# MainCtrl_A6_Pro.net
KiCad netlist of a schematic drawn in Altium Designer
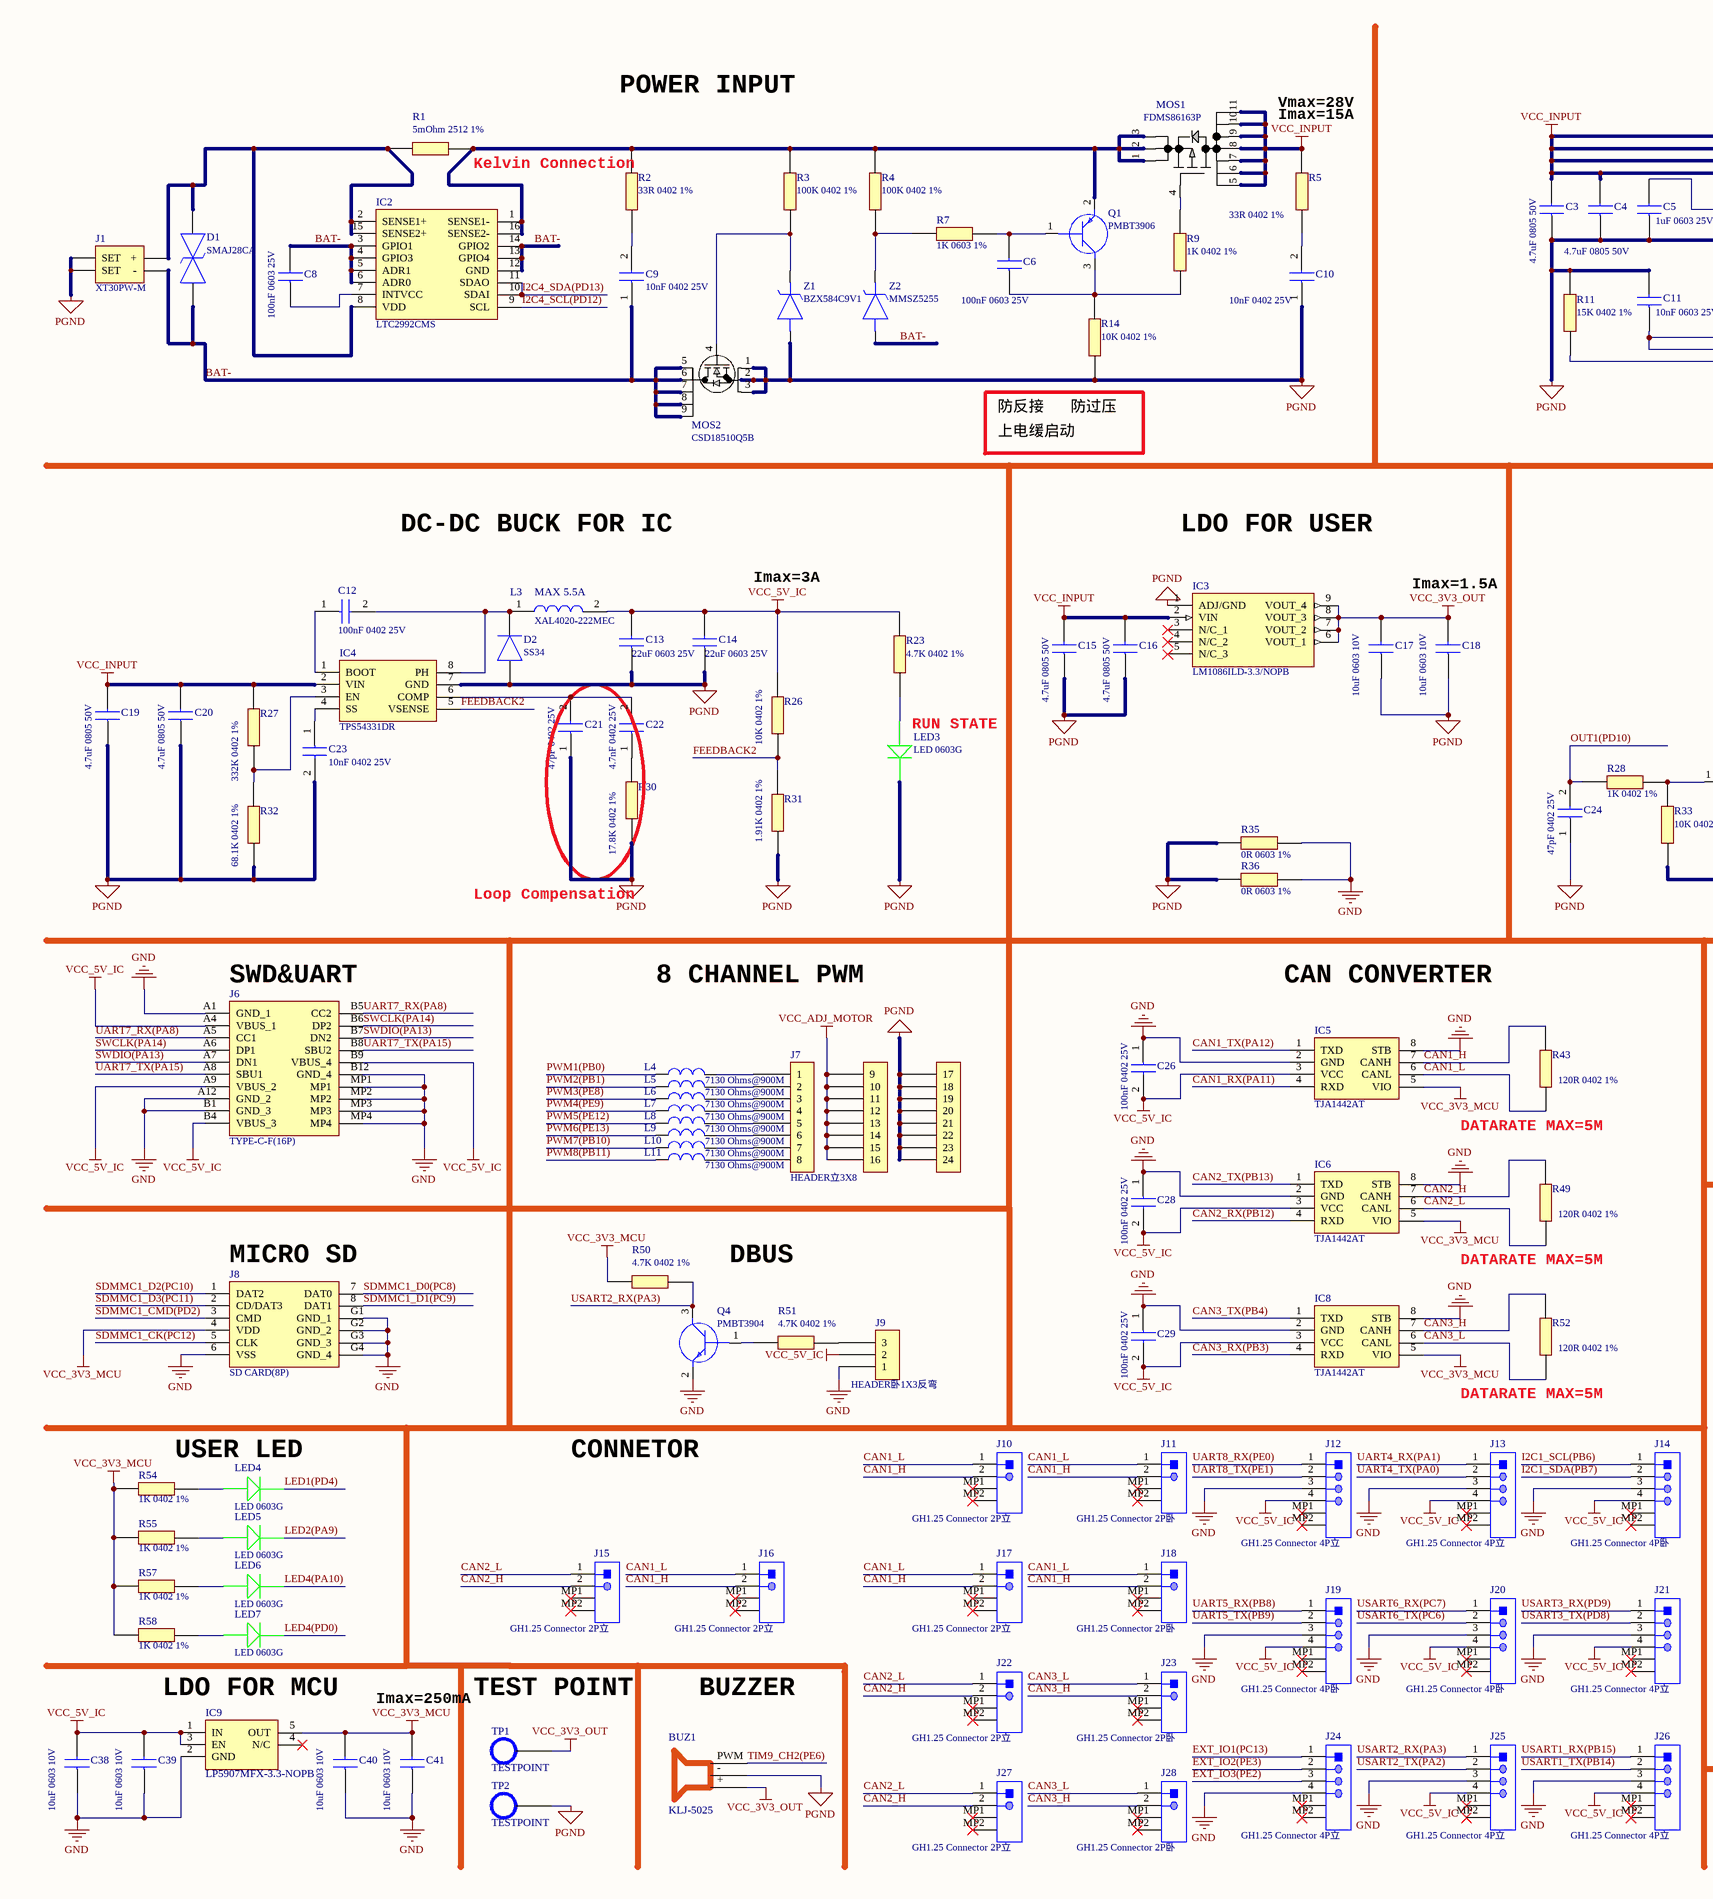
[diagram p0: MainCtrl A6 Pro.SchDoc, left]
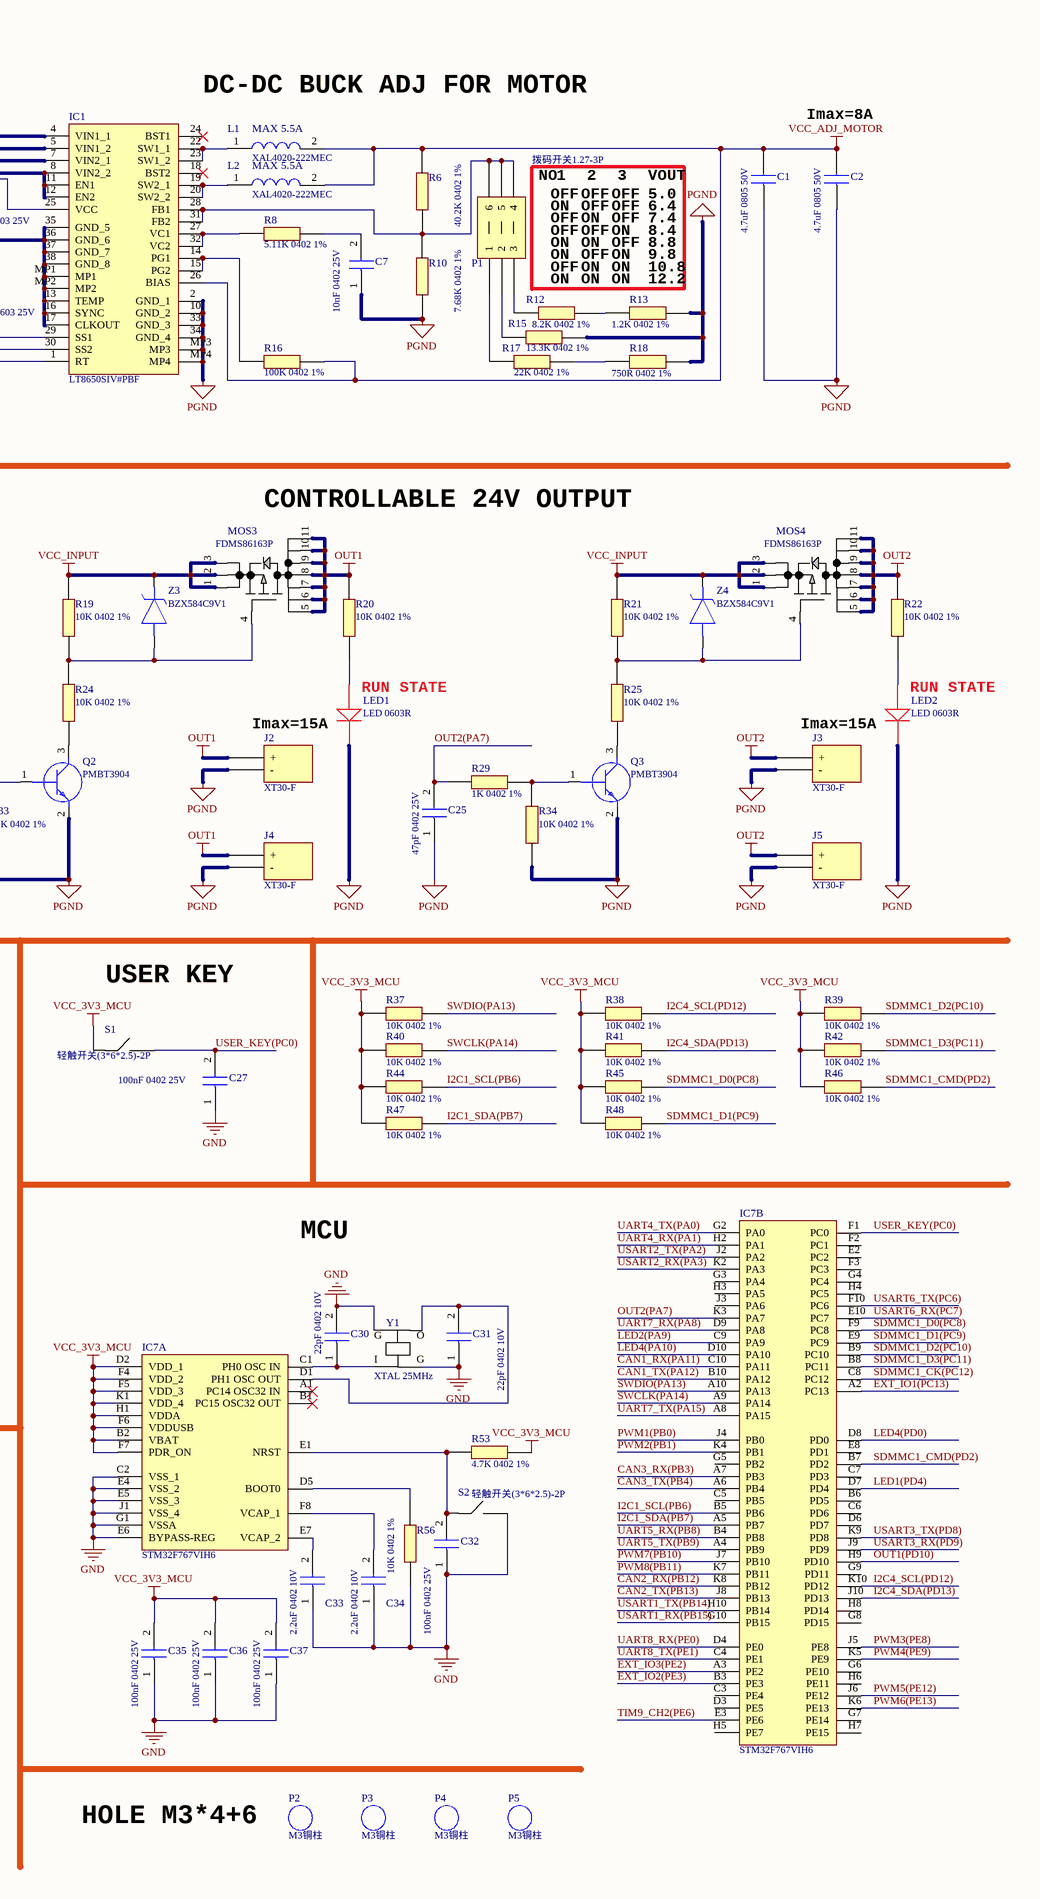
[diagram p1: MainCtrl A6 Pro.SchDoc, right]

(export (version "E")
  (design (tool "Eeschema 10.0.6"))
  (components
    (comp (ref "BUZ1")
      (value "KLJ-5025")
      (footprint "KLJ-5025")
      (description "Buzzer")
      (libsource (lib "Compilation") (part "KLJ-5025"))
    )
    (comp (ref "C1")
      (value "4.7uF 0805 50V")
      (footprint "C0805")
      (description "Capacitor")
      (fields
        (field (name "MANUFACTURER_PART_NUMBER") "0805B104K500CT")
        (field (name "MOUSER PART NUMBER") "791-0805B104K500CT")
      )
      (libsource (lib "Compilation") (part "C0805"))
    )
    (comp (ref "C2")
      (value "4.7uF 0805 50V")
      (footprint "C0805")
      (description "Capacitor")
      (fields
        (field (name "MANUFACTURER_PART_NUMBER") "0805B104K500CT")
        (field (name "MOUSER PART NUMBER") "791-0805B104K500CT")
      )
      (libsource (lib "Compilation") (part "C0805"))
    )
    (comp (ref "C3")
      (value "4.7uF 0805 50V")
      (footprint "C0805")
      (description "Capacitor")
      (fields
        (field (name "MANUFACTURER_PART_NUMBER") "0805B104K500CT")
        (field (name "MOUSER PART NUMBER") "791-0805B104K500CT")
      )
      (libsource (lib "Compilation") (part "C0805"))
    )
    (comp (ref "C4")
      (value "4.7uF 0805 50V")
      (footprint "C0805")
      (description "Capacitor")
      (fields
        (field (name "MANUFACTURER_PART_NUMBER") "0805B104K500CT")
        (field (name "MOUSER PART NUMBER") "791-0805B104K500CT")
      )
      (libsource (lib "Compilation") (part "C0805"))
    )
    (comp (ref "C5")
      (value "1uF 0603 25V")
      (footprint "C0603")
      (description "Capacitor")
      (fields
        (field (name "MANUFACTURER_PART_NUMBER") "0603N470J500CT")
        (field (name "MOUSER PART NUMBER") "791-0603N470J500CT")
      )
      (libsource (lib "Compilation") (part "C0603"))
    )
    (comp (ref "C6")
      (value "100nF 0603 25V")
      (footprint "C0603")
      (description "Capacitor")
      (fields
        (field (name "MANUFACTURER_PART_NUMBER") "0603N470J500CT")
        (field (name "MOUSER PART NUMBER") "791-0603N470J500CT")
      )
      (libsource (lib "Compilation") (part "C0603"))
    )
    (comp (ref "C7")
      (value "10nF 0402 25V")
      (footprint "C0402")
      (description "Capacitor")
      (libsource (lib "Compilation") (part "C0402"))
    )
    (comp (ref "C8")
      (value "100nF 0603 25V")
      (footprint "C0603")
      (description "Capacitor")
      (fields
        (field (name "MANUFACTURER_PART_NUMBER") "0603N470J500CT")
        (field (name "MOUSER PART NUMBER") "791-0603N470J500CT")
      )
      (libsource (lib "Compilation") (part "C0603"))
    )
    (comp (ref "C9")
      (value "10nF 0402 25V")
      (footprint "C0402")
      (description "Capacitor")
      (libsource (lib "Compilation") (part "C0402"))
    )
    (comp (ref "C10")
      (value "10nF 0402 25V")
      (footprint "C0402")
      (description "Capacitor")
      (libsource (lib "Compilation") (part "C0402"))
    )
    (comp (ref "C11")
      (value "10nF 0603 25V")
      (footprint "C0603")
      (description "Capacitor")
      (fields
        (field (name "MANUFACTURER_PART_NUMBER") "0603N470J500CT")
        (field (name "MOUSER PART NUMBER") "791-0603N470J500CT")
      )
      (libsource (lib "Compilation") (part "C0603"))
    )
    (comp (ref "C12")
      (value "100nF 0402 25V")
      (footprint "C0402")
      (description "Capacitor")
      (libsource (lib "Compilation") (part "C0402"))
    )
    (comp (ref "C13")
      (value "22uF 0603 25V")
      (footprint "C0603")
      (description "Capacitor")
      (fields
        (field (name "MANUFACTURER_PART_NUMBER") "0603N470J500CT")
        (field (name "MOUSER PART NUMBER") "791-0603N470J500CT")
      )
      (libsource (lib "Compilation") (part "C0603"))
    )
    (comp (ref "C14")
      (value "22uF 0603 25V")
      (footprint "C0603")
      (description "Capacitor")
      (fields
        (field (name "MANUFACTURER_PART_NUMBER") "0603N470J500CT")
        (field (name "MOUSER PART NUMBER") "791-0603N470J500CT")
      )
      (libsource (lib "Compilation") (part "C0603"))
    )
    (comp (ref "C15")
      (value "4.7uF 0805 50V")
      (footprint "C0805")
      (description "Capacitor")
      (fields
        (field (name "MANUFACTURER_PART_NUMBER") "0805B104K500CT")
        (field (name "MOUSER PART NUMBER") "791-0805B104K500CT")
      )
      (libsource (lib "Compilation") (part "C0805"))
    )
    (comp (ref "C16")
      (value "4.7uF 0805 50V")
      (footprint "C0805")
      (description "Capacitor")
      (fields
        (field (name "MANUFACTURER_PART_NUMBER") "0805B104K500CT")
        (field (name "MOUSER PART NUMBER") "791-0805B104K500CT")
      )
      (libsource (lib "Compilation") (part "C0805"))
    )
    (comp (ref "C17")
      (value "10uF 0603 10V")
      (footprint "C0603")
      (description "Capacitor")
      (fields
        (field (name "MANUFACTURER_PART_NUMBER") "0603N470J500CT")
        (field (name "MOUSER PART NUMBER") "791-0603N470J500CT")
      )
      (libsource (lib "Compilation") (part "C0603"))
    )
    (comp (ref "C18")
      (value "10uF 0603 10V")
      (footprint "C0603")
      (description "Capacitor")
      (fields
        (field (name "MANUFACTURER_PART_NUMBER") "0603N470J500CT")
        (field (name "MOUSER PART NUMBER") "791-0603N470J500CT")
      )
      (libsource (lib "Compilation") (part "C0603"))
    )
    (comp (ref "C19")
      (value "4.7uF 0805 50V")
      (footprint "C0805")
      (description "Capacitor")
      (fields
        (field (name "MANUFACTURER_PART_NUMBER") "0805B104K500CT")
        (field (name "MOUSER PART NUMBER") "791-0805B104K500CT")
      )
      (libsource (lib "Compilation") (part "C0805"))
    )
    (comp (ref "C20")
      (value "4.7uF 0805 50V")
      (footprint "C0805")
      (description "Capacitor")
      (fields
        (field (name "MANUFACTURER_PART_NUMBER") "0805B104K500CT")
        (field (name "MOUSER PART NUMBER") "791-0805B104K500CT")
      )
      (libsource (lib "Compilation") (part "C0805"))
    )
    (comp (ref "C21")
      (value "47pF 0402 25V")
      (footprint "C0402")
      (description "Capacitor")
      (libsource (lib "Compilation") (part "C0402"))
    )
    (comp (ref "C22")
      (value "4.7nF 0402 25V")
      (footprint "C0402")
      (description "Capacitor")
      (libsource (lib "Compilation") (part "C0402"))
    )
    (comp (ref "C23")
      (value "10nF 0402 25V")
      (footprint "C0402")
      (description "Capacitor")
      (libsource (lib "Compilation") (part "C0402"))
    )
    (comp (ref "C24")
      (value "47pF 0402 25V")
      (footprint "C0402")
      (description "Capacitor")
      (libsource (lib "Compilation") (part "C0402"))
    )
    (comp (ref "C25")
      (value "47pF 0402 25V")
      (footprint "C0402")
      (description "Capacitor")
      (libsource (lib "Compilation") (part "C0402"))
    )
    (comp (ref "C26")
      (value "100nF 0402 25V")
      (footprint "C0402")
      (description "Capacitor")
      (libsource (lib "Compilation") (part "C0402"))
    )
    (comp (ref "C27")
      (value "100nF 0402 25V")
      (footprint "C0402")
      (description "Capacitor")
      (libsource (lib "Compilation") (part "C0402"))
    )
    (comp (ref "C28")
      (value "100nF 0402 25V")
      (footprint "C0402")
      (description "Capacitor")
      (libsource (lib "Compilation") (part "C0402"))
    )
    (comp (ref "C29")
      (value "100nF 0402 25V")
      (footprint "C0402")
      (description "Capacitor")
      (libsource (lib "Compilation") (part "C0402"))
    )
    (comp (ref "C30")
      (value "22pF 0402 10V")
      (footprint "C0402")
      (description "Capacitor")
      (libsource (lib "Compilation") (part "C0402"))
    )
    (comp (ref "C31")
      (value "22pF 0402 10V")
      (footprint "C0402")
      (description "Capacitor")
      (libsource (lib "Compilation") (part "C0402"))
    )
    (comp (ref "C32")
      (value "100nF 0402 25V")
      (footprint "C0402")
      (description "Capacitor")
      (libsource (lib "Compilation") (part "C0402"))
    )
    (comp (ref "C33")
      (value "2.2uF 0402 10V")
      (footprint "C0402")
      (description "Capacitor")
      (libsource (lib "Compilation") (part "C0402"))
    )
    (comp (ref "C34")
      (value "2.2uF 0402 10V")
      (footprint "C0402")
      (description "Capacitor")
      (libsource (lib "Compilation") (part "C0402"))
    )
    (comp (ref "C35")
      (value "100nF 0402 25V")
      (footprint "C0402")
      (description "Capacitor")
      (libsource (lib "Compilation") (part "C0402"))
    )
    (comp (ref "C36")
      (value "100nF 0402 25V")
      (footprint "C0402")
      (description "Capacitor")
      (libsource (lib "Compilation") (part "C0402"))
    )
    (comp (ref "C37")
      (value "100nF 0402 25V")
      (footprint "C0402")
      (description "Capacitor")
      (libsource (lib "Compilation") (part "C0402"))
    )
    (comp (ref "C38")
      (value "10uF 0603 10V")
      (footprint "C0603")
      (description "Capacitor")
      (fields
        (field (name "MANUFACTURER_PART_NUMBER") "0603N470J500CT")
        (field (name "MOUSER PART NUMBER") "791-0603N470J500CT")
      )
      (libsource (lib "Compilation") (part "C0603"))
    )
    (comp (ref "C39")
      (value "10uF 0603 10V")
      (footprint "C0603")
      (description "Capacitor")
      (fields
        (field (name "MANUFACTURER_PART_NUMBER") "0603N470J500CT")
        (field (name "MOUSER PART NUMBER") "791-0603N470J500CT")
      )
      (libsource (lib "Compilation") (part "C0603"))
    )
    (comp (ref "C40")
      (value "10uF 0603 10V")
      (footprint "C0603")
      (description "Capacitor")
      (fields
        (field (name "MANUFACTURER_PART_NUMBER") "0603N470J500CT")
        (field (name "MOUSER PART NUMBER") "791-0603N470J500CT")
      )
      (libsource (lib "Compilation") (part "C0603"))
    )
    (comp (ref "C41")
      (value "10uF 0603 10V")
      (footprint "C0603")
      (description "Capacitor")
      (fields
        (field (name "MANUFACTURER_PART_NUMBER") "0603N470J500CT")
        (field (name "MOUSER PART NUMBER") "791-0603N470J500CT")
      )
      (libsource (lib "Compilation") (part "C0603"))
    )
    (comp (ref "D1")
      (value "SMAJ28CA")
      (footprint "SMAJ28CA")
      (description "TVS Diode (Bi-directional)")
      (fields (field (name "MOUSER PART NUMBER") "652-SMAJ28CA"))
      (libsource (lib "Compilation") (part "SMAJ28CA"))
    )
    (comp (ref "D2")
      (value "SS34")
      (footprint "SS34")
      (description "Diode")
      (fields
        (field (name "MANUFACTURER_PART_NUMBER") "SS34LWHRVG")
        (field (name "MOUSER PART NUMBER") "821-SS34LWHRVG")
      )
      (libsource (lib "Compilation") (part "SS34"))
    )
    (comp (ref "IC1")
      (value "LT8650SIV#PBF")
      (footprint "Compilation:LT8650SEV#PBF")
      (description "Integrated Circuit")
      (fields (field (name "MOUSER PART NUMBER") "584-LT8650SIVPBF"))
      (libsource (lib "Compilation") (part "LT8650SIV#PBF"))
    )
    (comp (ref "IC2")
      (value "LTC2992CMS")
      (footprint "Compilation:LTC2992CMS")
      (description "Integrated Circuit")
      (fields
        (field (name "MANUFACTURER_PART_NUMBER") "LTC2992CMS#TRPBF")
        (field (name "MOUSER PART NUMBER") "584-LTC2992CMSTRPBF")
      )
      (libsource (lib "Compilation") (part "LTC2992CMS"))
    )
    (comp (ref "IC3")
      (value "LM1086ILD-3.3/NOPB")
      (footprint "Compilation:LM1086ILD-3.3")
      (description "Integrated Circuit")
      (fields (field (name "MOUSER PART NUMBER") "926-LM1086ILD33NOPB"))
      (libsource (lib "Compilation") (part "LM1086ILD-3.3/NOPB"))
    )
    (comp (ref "IC4")
      (value "TPS54331DR")
      (footprint "TPS54331DR")
      (description "Integrated Circuit")
      (fields (field (name "MOUSER PART NUMBER") "595-TPS54331DR"))
      (libsource (lib "Compilation") (part "TPS54331DR"))
    )
    (comp (ref "IC5")
      (value "TJA1442AT")
      (footprint "Compilation:TJA1442AT")
      (description "Integrated Circuit")
      (fields (field (name "MANUFACTURER_PART_NUMBER") "TJA1442AT/0Z"))
      (libsource (lib "Compilation") (part "TJA1442AT"))
    )
    (comp (ref "IC6")
      (value "TJA1442AT")
      (footprint "Compilation:TJA1442AT")
      (description "Integrated Circuit")
      (fields (field (name "MANUFACTURER_PART_NUMBER") "TJA1442AT/0Z"))
      (libsource (lib "Compilation") (part "TJA1442AT"))
    )
    (comp (ref "IC7")
      (value "STM32F767VIH6")
      (footprint "Compilation:STM32F767VIH6")
      (description "Integrated Circuit")
      (fields (field (name "MOUSER PART NUMBER") "511-STM32F767VIH6"))
      (libsource (lib "Compilation") (part "STM32F767VIH6"))
    )
    (comp (ref "IC8")
      (value "TJA1442AT")
      (footprint "Compilation:TJA1442AT")
      (description "Integrated Circuit")
      (fields (field (name "MANUFACTURER_PART_NUMBER") "TJA1442AT/0Z"))
      (libsource (lib "Compilation") (part "TJA1442AT"))
    )
    (comp (ref "IC9")
      (value "LP5907MFX-3.3-NOPB")
      (footprint "LP5907MFX-3.3")
      (description "Integrated Circuit")
      (fields
        (field (name "MANUFACTURER_PART_NUMBER") "LP5907MFX-3.3/NOPB")
        (field (name "MOUSER PART NUMBER") "595-LP5907MFX-3.3NPB")
      )
      (libsource (lib "Compilation") (part "LP5907MFX-3.3-NOPB"))
    )
    (comp (ref "J1")
      (value "XT30PW-M")
      (footprint "XT30PW-M")
      (description "Connector")
      (libsource (lib "Compilation") (part "XT30PW-M"))
    )
    (comp (ref "J2")
      (value "XT30-F")
      (footprint "XT30-F")
      (description "Connector")
      (libsource (lib "Compilation") (part "XT30-F"))
    )
    (comp (ref "J3")
      (value "XT30-F")
      (footprint "XT30-F")
      (description "Connector")
      (libsource (lib "Compilation") (part "XT30-F"))
    )
    (comp (ref "J4")
      (value "XT30-F")
      (footprint "XT30-F")
      (description "Connector")
      (libsource (lib "Compilation") (part "XT30-F"))
    )
    (comp (ref "J5")
      (value "XT30-F")
      (footprint "XT30-F")
      (description "Connector")
      (libsource (lib "Compilation") (part "XT30-F"))
    )
    (comp (ref "J6")
      (value "TYPE-C-F(16P)")
      (footprint "TYPE-C-F(16P)")
      (description "Connector")
      (fields (field (name "MANUFACTURER_PART_NUMBER") "TYPEC-304S-ACP16"))
      (libsource (lib "Compilation") (part "TYPE-C-F(16P)"))
    )
    (comp (ref "J7")
      (value "HEADER立3X8")
      (footprint "Header立3X8")
      (description "Header")
      (libsource (lib "Compilation") (part "HEADER立3X8"))
    )
    (comp (ref "J8")
      (value "SD CARD(8P)")
      (footprint "SD CARD(8P)")
      (description "Connector")
      (fields (field (name "MANUFACTURER_PART_NUMBER") "0472192001"))
      (libsource (lib "Compilation") (part "SD CARD(8P)"))
    )
    (comp (ref "J9")
      (value "HEADER卧1X3反弯")
      (footprint "Header卧1X3反弯")
      (description "Header")
      (libsource (lib "Compilation") (part "HEADER卧1X3反弯"))
    )
    (comp (ref "J10")
      (value "GH1.25 Connector 2P立")
      (footprint "GH1.25立2P")
      (description "GH1.25 Connector")
      (fields (field (name "MANUFACTURER") "JST"))
      (libsource (lib "Compilation") (part "GH1.25 Connector 2P立"))
    )
    (comp (ref "J11")
      (value "GH1.25 Connector 2P卧")
      (footprint "GH1.25卧2P")
      (description "GH1.25 Connector")
      (fields (field (name "MANUFACTURER") "JST"))
      (libsource (lib "Compilation") (part "GH1.25 Connector 2P卧"))
    )
    (comp (ref "J12")
      (value "GH1.25 Connector 4P立")
      (footprint "GH1.25立4P")
      (description "GH1.25 Connector")
      (fields (field (name "MANUFACTURER") "JST"))
      (libsource (lib "Compilation") (part "GH1.25 Connector 4P立"))
    )
    (comp (ref "J13")
      (value "GH1.25 Connector 4P立")
      (footprint "GH1.25立4P")
      (description "GH1.25 Connector")
      (fields (field (name "MANUFACTURER") "JST"))
      (libsource (lib "Compilation") (part "GH1.25 Connector 4P立"))
    )
    (comp (ref "J14")
      (value "GH1.25 Connector 4P卧")
      (footprint "GH1.25卧4P")
      (description "GH1.25 Connector")
      (fields (field (name "MANUFACTURER") "JST"))
      (libsource (lib "Compilation") (part "GH1.25 Connector 4P卧"))
    )
    (comp (ref "J15")
      (value "GH1.25 Connector 2P立")
      (footprint "GH1.25立2P")
      (description "GH1.25 Connector")
      (fields (field (name "MANUFACTURER") "JST"))
      (libsource (lib "Compilation") (part "GH1.25 Connector 2P立"))
    )
    (comp (ref "J16")
      (value "GH1.25 Connector 2P立")
      (footprint "GH1.25立2P")
      (description "GH1.25 Connector")
      (fields (field (name "MANUFACTURER") "JST"))
      (libsource (lib "Compilation") (part "GH1.25 Connector 2P立"))
    )
    (comp (ref "J17")
      (value "GH1.25 Connector 2P立")
      (footprint "GH1.25立2P")
      (description "GH1.25 Connector")
      (fields (field (name "MANUFACTURER") "JST"))
      (libsource (lib "Compilation") (part "GH1.25 Connector 2P立"))
    )
    (comp (ref "J18")
      (value "GH1.25 Connector 2P卧")
      (footprint "GH1.25卧2P")
      (description "GH1.25 Connector")
      (fields (field (name "MANUFACTURER") "JST"))
      (libsource (lib "Compilation") (part "GH1.25 Connector 2P卧"))
    )
    (comp (ref "J19")
      (value "GH1.25 Connector 4P卧")
      (footprint "GH1.25卧4P")
      (description "GH1.25 Connector")
      (fields (field (name "MANUFACTURER") "JST"))
      (libsource (lib "Compilation") (part "GH1.25 Connector 4P卧"))
    )
    (comp (ref "J20")
      (value "GH1.25 Connector 4P卧")
      (footprint "GH1.25卧4P")
      (description "GH1.25 Connector")
      (fields (field (name "MANUFACTURER") "JST"))
      (libsource (lib "Compilation") (part "GH1.25 Connector 4P卧"))
    )
    (comp (ref "J21")
      (value "GH1.25 Connector 4P立")
      (footprint "GH1.25立4P")
      (description "GH1.25 Connector")
      (fields (field (name "MANUFACTURER") "JST"))
      (libsource (lib "Compilation") (part "GH1.25 Connector 4P立"))
    )
    (comp (ref "J22")
      (value "GH1.25 Connector 2P立")
      (footprint "GH1.25立2P")
      (description "GH1.25 Connector")
      (fields (field (name "MANUFACTURER") "JST"))
      (libsource (lib "Compilation") (part "GH1.25 Connector 2P立"))
    )
    (comp (ref "J23")
      (value "GH1.25 Connector 2P卧")
      (footprint "GH1.25卧2P")
      (description "GH1.25 Connector")
      (fields (field (name "MANUFACTURER") "JST"))
      (libsource (lib "Compilation") (part "GH1.25 Connector 2P卧"))
    )
    (comp (ref "J24")
      (value "GH1.25 Connector 4P立")
      (footprint "GH1.25立4P")
      (description "GH1.25 Connector")
      (fields (field (name "MANUFACTURER") "JST"))
      (libsource (lib "Compilation") (part "GH1.25 Connector 4P立"))
    )
    (comp (ref "J25")
      (value "GH1.25 Connector 4P立")
      (footprint "GH1.25立4P")
      (description "GH1.25 Connector")
      (fields (field (name "MANUFACTURER") "JST"))
      (libsource (lib "Compilation") (part "GH1.25 Connector 4P立"))
    )
    (comp (ref "J26")
      (value "GH1.25 Connector 4P立")
      (footprint "GH1.25立4P")
      (description "GH1.25 Connector")
      (fields (field (name "MANUFACTURER") "JST"))
      (libsource (lib "Compilation") (part "GH1.25 Connector 4P立"))
    )
    (comp (ref "J27")
      (value "GH1.25 Connector 2P立")
      (footprint "GH1.25立2P")
      (description "GH1.25 Connector")
      (fields (field (name "MANUFACTURER") "JST"))
      (libsource (lib "Compilation") (part "GH1.25 Connector 2P立"))
    )
    (comp (ref "J28")
      (value "GH1.25 Connector 2P卧")
      (footprint "GH1.25卧2P")
      (description "GH1.25 Connector")
      (fields (field (name "MANUFACTURER") "JST"))
      (libsource (lib "Compilation") (part "GH1.25 Connector 2P卧"))
    )
    (comp (ref "L1")
      (value "XAL4020-222MEC")
      (footprint "Compilation:XAL4020")
      (description "Inductor")
      (fields
        (field (name "MANUFACTURER_PART_NUMBER") "XAL4020-222MEB")
        (field (name "MOUSER PART NUMBER") "994-XAL4020-222MEB")
      )
      (libsource (lib "Compilation") (part "XAL4020-222MEC"))
    )
    (comp (ref "L2")
      (value "XAL4020-222MEC")
      (footprint "Compilation:XAL4020")
      (description "Inductor")
      (fields
        (field (name "MANUFACTURER_PART_NUMBER") "XAL4020-222MEB")
        (field (name "MOUSER PART NUMBER") "994-XAL4020-222MEB")
      )
      (libsource (lib "Compilation") (part "XAL4020-222MEC"))
    )
    (comp (ref "L3")
      (value "XAL4020-222MEC")
      (footprint "Compilation:XAL4020")
      (description "Inductor")
      (fields
        (field (name "MANUFACTURER_PART_NUMBER") "XAL4020-222MEB")
        (field (name "MOUSER PART NUMBER") "994-XAL4020-222MEB")
      )
      (libsource (lib "Compilation") (part "XAL4020-222MEC"))
    )
    (comp (ref "L4")
      (value "7130 Ohms@900M")
      (footprint "Compilation:0402DF")
      (description "Inductor 901XJR")
      (libsource (lib "Compilation") (part "Ferrite Chip Inductors"))
    )
    (comp (ref "L5")
      (value "7130 Ohms@900M")
      (footprint "Compilation:0402DF")
      (description "Inductor 901XJR")
      (libsource (lib "Compilation") (part "Ferrite Chip Inductors"))
    )
    (comp (ref "L6")
      (value "7130 Ohms@900M")
      (footprint "Compilation:0402DF")
      (description "Inductor 901XJR")
      (libsource (lib "Compilation") (part "Ferrite Chip Inductors"))
    )
    (comp (ref "L7")
      (value "7130 Ohms@900M")
      (footprint "Compilation:0402DF")
      (description "Inductor 901XJR")
      (libsource (lib "Compilation") (part "Ferrite Chip Inductors"))
    )
    (comp (ref "L8")
      (value "7130 Ohms@900M")
      (footprint "Compilation:0402DF")
      (description "Inductor 901XJR")
      (libsource (lib "Compilation") (part "Ferrite Chip Inductors"))
    )
    (comp (ref "L9")
      (value "7130 Ohms@900M")
      (footprint "Compilation:0402DF")
      (description "Inductor 901XJR")
      (libsource (lib "Compilation") (part "Ferrite Chip Inductors"))
    )
    (comp (ref "L10")
      (value "7130 Ohms@900M")
      (footprint "Compilation:0402DF")
      (description "Inductor 901XJR")
      (libsource (lib "Compilation") (part "Ferrite Chip Inductors"))
    )
    (comp (ref "L11")
      (value "7130 Ohms@900M")
      (footprint "Compilation:0402DF")
      (description "Inductor 901XJR")
      (libsource (lib "Compilation") (part "Ferrite Chip Inductors"))
    )
    (comp (ref "LED1")
      (value "LED 0603R")
      (footprint "LED 0603R")
      (description "LED Red")
      (libsource (lib "Compilation") (part "LED 0603R"))
    )
    (comp (ref "LED2")
      (value "LED 0603R")
      (footprint "LED 0603R")
      (description "LED Red")
      (libsource (lib "Compilation") (part "LED 0603R"))
    )
    (comp (ref "LED3")
      (value "LED 0603G")
      (footprint "LED 0603G")
      (description "LED Green")
      (libsource (lib "Compilation") (part "LED 0603G"))
    )
    (comp (ref "LED4")
      (value "LED 0603G")
      (footprint "LED 0603G")
      (description "LED Green")
      (libsource (lib "Compilation") (part "LED 0603G"))
    )
    (comp (ref "LED5")
      (value "LED 0603G")
      (footprint "LED 0603G")
      (description "LED Green")
      (libsource (lib "Compilation") (part "LED 0603G"))
    )
    (comp (ref "LED6")
      (value "LED 0603G")
      (footprint "LED 0603G")
      (description "LED Green")
      (libsource (lib "Compilation") (part "LED 0603G"))
    )
    (comp (ref "LED7")
      (value "LED 0603G")
      (footprint "LED 0603G")
      (description "LED Green")
      (libsource (lib "Compilation") (part "LED 0603G"))
    )
    (comp (ref "MOS1")
      (value "FDMS86163P")
      (footprint "FDMS86163P")
      (description "MOSFET P-ch")
      (fields
        (field (name "MANUFACTURER_PART_NUMBER") "FDMS86252")
        (field (name "MOUSER PART NUMBER") "512-FDMS86252")
      )
      (libsource (lib "Compilation") (part "FDMS86163P"))
    )
    (comp (ref "MOS2")
      (value "CSD18510Q5B")
      (footprint "CSD18510Q5B")
      (description "MOSFET N-ch")
      (fields
        (field (name "MANUFACTURER_PART_NUMBER") "CSD18510Q5BT")
        (field (name "MOUSER PART NUMBER") "595-CSD18510Q5BT")
      )
      (libsource (lib "Compilation") (part "CSD18510Q5B"))
    )
    (comp (ref "MOS3")
      (value "FDMS86163P")
      (footprint "FDMS86163P")
      (description "MOSFET P-ch")
      (fields
        (field (name "MANUFACTURER_PART_NUMBER") "FDMS86252")
        (field (name "MOUSER PART NUMBER") "512-FDMS86252")
      )
      (libsource (lib "Compilation") (part "FDMS86163P"))
    )
    (comp (ref "MOS4")
      (value "FDMS86163P")
      (footprint "FDMS86163P")
      (description "MOSFET P-ch")
      (fields
        (field (name "MANUFACTURER_PART_NUMBER") "FDMS86252")
        (field (name "MOUSER PART NUMBER") "512-FDMS86252")
      )
      (libsource (lib "Compilation") (part "FDMS86163P"))
    )
    (comp (ref "P1")
      (value "拨码开关1.27-3P")
      (footprint "拨码开关1.27-3P")
      (description "Switch")
      (libsource (lib "Compilation") (part "拨码开关1.27-3P"))
    )
    (comp (ref "P2")
      (value "M3铜柱")
      (footprint "M3x4+6铜柱")
      (description "Hole M3X4+6")
      (libsource (lib "Compilation") (part "M3铜柱"))
    )
    (comp (ref "P3")
      (value "M3铜柱")
      (footprint "M3x4+6铜柱")
      (description "Hole M3X4+6")
      (libsource (lib "Compilation") (part "M3铜柱"))
    )
    (comp (ref "P4")
      (value "M3铜柱")
      (footprint "M3x4+6铜柱")
      (description "Hole M3X4+6")
      (libsource (lib "Compilation") (part "M3铜柱"))
    )
    (comp (ref "P5")
      (value "M3铜柱")
      (footprint "M3x4+6铜柱")
      (description "Hole M3X4+6")
      (libsource (lib "Compilation") (part "M3铜柱"))
    )
    (comp (ref "Q1")
      (value "PMBT3906")
      (footprint "PMBT3906")
      (description "Transistor BJT PNP")
      (fields
        (field (name "MANUFACTURER_PART_NUMBER") "PMBT3906,235")
        (field (name "MOUSER PART NUMBER") "771-PMBT3906235")
      )
      (libsource (lib "Compilation") (part "PMBT3906"))
    )
    (comp (ref "Q2")
      (value "PMBT3904")
      (footprint "PMBT3904")
      (description "Transistor BJT NPN")
      (fields
        (field (name "MANUFACTURER_PART_NUMBER") "PMBT3904,215")
        (field (name "MOUSER PART NUMBER") "771-PMBT3904-T/R")
      )
      (libsource (lib "Compilation") (part "PMBT3904"))
    )
    (comp (ref "Q3")
      (value "PMBT3904")
      (footprint "PMBT3904")
      (description "Transistor BJT NPN")
      (fields
        (field (name "MANUFACTURER_PART_NUMBER") "PMBT3904,215")
        (field (name "MOUSER PART NUMBER") "771-PMBT3904-T/R")
      )
      (libsource (lib "Compilation") (part "PMBT3904"))
    )
    (comp (ref "Q4")
      (value "PMBT3904")
      (footprint "PMBT3904")
      (description "Transistor BJT NPN")
      (fields
        (field (name "MANUFACTURER_PART_NUMBER") "PMBT3904,215")
        (field (name "MOUSER PART NUMBER") "771-PMBT3904-T/R")
      )
      (libsource (lib "Compilation") (part "PMBT3904"))
    )
    (comp (ref "R1")
      (value "5mOhm 2512 1%")
      (footprint "R2512")
      (description "Resistor")
      (libsource (lib "Compilation") (part "R2512"))
    )
    (comp (ref "R2")
      (value "33R 0402 1%")
      (footprint "R0402")
      (description "Resistor")
      (fields (field (name "MANUFACTURER_PART_NUMBER") "CR0402"))
      (libsource (lib "") (part "R0402_3"))
    )
    (comp (ref "R3")
      (value "100K 0402 1%")
      (footprint "R0402")
      (description "Resistor")
      (fields (field (name "MANUFACTURER_PART_NUMBER") "CR0402"))
      (libsource (lib "") (part "R0402_3"))
    )
    (comp (ref "R4")
      (value "100K 0402 1%")
      (footprint "R0402")
      (description "Resistor")
      (fields (field (name "MANUFACTURER_PART_NUMBER") "CR0402"))
      (libsource (lib "") (part "R0402_3"))
    )
    (comp (ref "R5")
      (value "33R 0402 1%")
      (footprint "R0402")
      (description "Resistor")
      (fields (field (name "MANUFACTURER_PART_NUMBER") "CR0402"))
      (libsource (lib "") (part "R0402_3"))
    )
    (comp (ref "R6")
      (value "40.2K 0402 1%")
      (footprint "R0402")
      (description "Resistor")
      (fields (field (name "MANUFACTURER_PART_NUMBER") "CR0402"))
      (libsource (lib "") (part "R0402_2"))
    )
    (comp (ref "R7")
      (value "1K 0603 1%")
      (footprint "R0603")
      (description "Resistor")
      (fields (field (name "MANUFACTURER_PART_NUMBER") "CR0603-JW-681ELF"))
      (libsource (lib "Compilation") (part "R0603"))
    )
    (comp (ref "R8")
      (value "5.11K 0402 1%")
      (footprint "R0402")
      (description "Resistor")
      (fields (field (name "MANUFACTURER_PART_NUMBER") "CR0402"))
      (libsource (lib "") (part "R0402_1"))
    )
    (comp (ref "R9")
      (value "1K 0402 1%")
      (footprint "R0402")
      (description "Resistor")
      (fields (field (name "MANUFACTURER_PART_NUMBER") "CR0402"))
      (libsource (lib "") (part "R0402_3"))
    )
    (comp (ref "R10")
      (value "7.68K 0402 1%")
      (footprint "R0402")
      (description "Resistor")
      (fields (field (name "MANUFACTURER_PART_NUMBER") "CR0402"))
      (libsource (lib "") (part "R0402_2"))
    )
    (comp (ref "R11")
      (value "15K 0402 1%")
      (footprint "R0402")
      (description "Resistor")
      (fields (field (name "MANUFACTURER_PART_NUMBER") "CR0402"))
      (libsource (lib "") (part "R0402_2"))
    )
    (comp (ref "R12")
      (value "8.2K 0402 1%")
      (footprint "R0402")
      (description "Resistor")
      (fields (field (name "MANUFACTURER_PART_NUMBER") "CR0402"))
      (libsource (lib "") (part "R0402_1"))
    )
    (comp (ref "R13")
      (value "1.2K 0402 1%")
      (footprint "R0402")
      (description "Resistor")
      (fields (field (name "MANUFACTURER_PART_NUMBER") "CR0402"))
      (libsource (lib "") (part "R0402_1"))
    )
    (comp (ref "R14")
      (value "10K 0402 1%")
      (footprint "R0402")
      (description "Resistor")
      (fields (field (name "MANUFACTURER_PART_NUMBER") "CR0402"))
      (libsource (lib "") (part "R0402_3"))
    )
    (comp (ref "R15")
      (value "13.3K 0402 1%")
      (footprint "R0402")
      (description "Resistor")
      (fields (field (name "MANUFACTURER_PART_NUMBER") "CR0402"))
      (libsource (lib "") (part "R0402_1"))
    )
    (comp (ref "R16")
      (value "100K 0402 1%")
      (footprint "R0402")
      (description "Resistor")
      (fields (field (name "MANUFACTURER_PART_NUMBER") "CR0402"))
      (libsource (lib "") (part "R0402_1"))
    )
    (comp (ref "R17")
      (value "22K 0402 1%")
      (footprint "R0402")
      (description "Resistor")
      (fields (field (name "MANUFACTURER_PART_NUMBER") "CR0402"))
      (libsource (lib "") (part "R0402_1"))
    )
    (comp (ref "R18")
      (value "750R 0402 1%")
      (footprint "R0402")
      (description "Resistor")
      (fields (field (name "MANUFACTURER_PART_NUMBER") "CR0402"))
      (libsource (lib "") (part "R0402_1"))
    )
    (comp (ref "R19")
      (value "10K 0402 1%")
      (footprint "R0402")
      (description "Resistor")
      (fields (field (name "MANUFACTURER_PART_NUMBER") "CR0402"))
      (libsource (lib "") (part "R0402_2"))
    )
    (comp (ref "R20")
      (value "10K 0402 1%")
      (footprint "R0402")
      (description "Resistor")
      (fields (field (name "MANUFACTURER_PART_NUMBER") "CR0402"))
      (libsource (lib "") (part "R0402_2"))
    )
    (comp (ref "R21")
      (value "10K 0402 1%")
      (footprint "R0402")
      (description "Resistor")
      (fields (field (name "MANUFACTURER_PART_NUMBER") "CR0402"))
      (libsource (lib "") (part "R0402_2"))
    )
    (comp (ref "R22")
      (value "10K 0402 1%")
      (footprint "R0402")
      (description "Resistor")
      (fields (field (name "MANUFACTURER_PART_NUMBER") "CR0402"))
      (libsource (lib "") (part "R0402_2"))
    )
    (comp (ref "R23")
      (value "4.7K 0402 1%")
      (footprint "R0402")
      (description "Resistor")
      (fields (field (name "MANUFACTURER_PART_NUMBER") "CR0402"))
      (libsource (lib "") (part "R0402_2"))
    )
    (comp (ref "R24")
      (value "10K 0402 1%")
      (footprint "R0402")
      (description "Resistor")
      (fields (field (name "MANUFACTURER_PART_NUMBER") "CR0402"))
      (libsource (lib "") (part "R0402_2"))
    )
    (comp (ref "R25")
      (value "10K 0402 1%")
      (footprint "R0402")
      (description "Resistor")
      (fields (field (name "MANUFACTURER_PART_NUMBER") "CR0402"))
      (libsource (lib "") (part "R0402_2"))
    )
    (comp (ref "R26")
      (value "10K 0402 1%")
      (footprint "R0402")
      (description "Resistor")
      (fields (field (name "MANUFACTURER_PART_NUMBER") "CR0402"))
      (libsource (lib "") (part "R0402_3"))
    )
    (comp (ref "R27")
      (value "332K 0402 1%")
      (footprint "R0402")
      (description "Resistor")
      (fields (field (name "MANUFACTURER_PART_NUMBER") "CR0402"))
      (libsource (lib "") (part "R0402_3"))
    )
    (comp (ref "R28")
      (value "1K 0402 1%")
      (footprint "R0402")
      (description "Resistor")
      (fields (field (name "MANUFACTURER_PART_NUMBER") "CR0402"))
      (libsource (lib "Compilation") (part "R0402"))
    )
    (comp (ref "R29")
      (value "1K 0402 1%")
      (footprint "R0402")
      (description "Resistor")
      (fields (field (name "MANUFACTURER_PART_NUMBER") "CR0402"))
      (libsource (lib "Compilation") (part "R0402"))
    )
    (comp (ref "R30")
      (value "17.8K 0402 1%")
      (footprint "R0402")
      (description "Resistor")
      (fields (field (name "MANUFACTURER_PART_NUMBER") "CR0402"))
      (libsource (lib "") (part "R0402_3"))
    )
    (comp (ref "R31")
      (value "1.91K 0402 1%")
      (footprint "R0402")
      (description "Resistor")
      (fields (field (name "MANUFACTURER_PART_NUMBER") "CR0402"))
      (libsource (lib "") (part "R0402_3"))
    )
    (comp (ref "R32")
      (value "68.1K 0402 1%")
      (footprint "R0402")
      (description "Resistor")
      (fields (field (name "MANUFACTURER_PART_NUMBER") "CR0402"))
      (libsource (lib "") (part "R0402_3"))
    )
    (comp (ref "R33")
      (value "10K 0402 1%")
      (footprint "R0402")
      (description "Resistor")
      (fields (field (name "MANUFACTURER_PART_NUMBER") "CR0402"))
      (libsource (lib "") (part "R0402_2"))
    )
    (comp (ref "R34")
      (value "10K 0402 1%")
      (footprint "R0402")
      (description "Resistor")
      (fields (field (name "MANUFACTURER_PART_NUMBER") "CR0402"))
      (libsource (lib "") (part "R0402_2"))
    )
    (comp (ref "R35")
      (value "0R 0603 1%")
      (footprint "R0603")
      (description "Resistor")
      (fields (field (name "MANUFACTURER_PART_NUMBER") "CR0603-JW-681ELF"))
      (libsource (lib "Compilation") (part "R0603"))
    )
    (comp (ref "R36")
      (value "0R 0603 1%")
      (footprint "R0603")
      (description "Resistor")
      (fields (field (name "MANUFACTURER_PART_NUMBER") "CR0603-JW-681ELF"))
      (libsource (lib "Compilation") (part "R0603"))
    )
    (comp (ref "R37")
      (value "10K 0402 1%")
      (footprint "R0402")
      (description "Resistor")
      (fields (field (name "MANUFACTURER_PART_NUMBER") "CR0402"))
      (libsource (lib "Compilation") (part "R0402"))
    )
    (comp (ref "R38")
      (value "10K 0402 1%")
      (footprint "R0402")
      (description "Resistor")
      (fields (field (name "MANUFACTURER_PART_NUMBER") "CR0402"))
      (libsource (lib "Compilation") (part "R0402"))
    )
    (comp (ref "R39")
      (value "10K 0402 1%")
      (footprint "R0402")
      (description "Resistor")
      (fields (field (name "MANUFACTURER_PART_NUMBER") "CR0402"))
      (libsource (lib "Compilation") (part "R0402"))
    )
    (comp (ref "R40")
      (value "10K 0402 1%")
      (footprint "R0402")
      (description "Resistor")
      (fields (field (name "MANUFACTURER_PART_NUMBER") "CR0402"))
      (libsource (lib "Compilation") (part "R0402"))
    )
    (comp (ref "R41")
      (value "10K 0402 1%")
      (footprint "R0402")
      (description "Resistor")
      (fields (field (name "MANUFACTURER_PART_NUMBER") "CR0402"))
      (libsource (lib "Compilation") (part "R0402"))
    )
    (comp (ref "R42")
      (value "10K 0402 1%")
      (footprint "R0402")
      (description "Resistor")
      (fields (field (name "MANUFACTURER_PART_NUMBER") "CR0402"))
      (libsource (lib "Compilation") (part "R0402"))
    )
    (comp (ref "R43")
      (value "120R 0402 1%")
      (footprint "R0402")
      (description "Resistor")
      (fields (field (name "MANUFACTURER_PART_NUMBER") "CR0402"))
      (libsource (lib "") (part "R0402_3"))
    )
    (comp (ref "R44")
      (value "10K 0402 1%")
      (footprint "R0402")
      (description "Resistor")
      (fields (field (name "MANUFACTURER_PART_NUMBER") "CR0402"))
      (libsource (lib "Compilation") (part "R0402"))
    )
    (comp (ref "R45")
      (value "10K 0402 1%")
      (footprint "R0402")
      (description "Resistor")
      (fields (field (name "MANUFACTURER_PART_NUMBER") "CR0402"))
      (libsource (lib "Compilation") (part "R0402"))
    )
    (comp (ref "R46")
      (value "10K 0402 1%")
      (footprint "R0402")
      (description "Resistor")
      (fields (field (name "MANUFACTURER_PART_NUMBER") "CR0402"))
      (libsource (lib "Compilation") (part "R0402"))
    )
    (comp (ref "R47")
      (value "10K 0402 1%")
      (footprint "R0402")
      (description "Resistor")
      (fields (field (name "MANUFACTURER_PART_NUMBER") "CR0402"))
      (libsource (lib "Compilation") (part "R0402"))
    )
    (comp (ref "R48")
      (value "10K 0402 1%")
      (footprint "R0402")
      (description "Resistor")
      (fields (field (name "MANUFACTURER_PART_NUMBER") "CR0402"))
      (libsource (lib "Compilation") (part "R0402"))
    )
    (comp (ref "R49")
      (value "120R 0402 1%")
      (footprint "R0402")
      (description "Resistor")
      (fields (field (name "MANUFACTURER_PART_NUMBER") "CR0402"))
      (libsource (lib "") (part "R0402_3"))
    )
    (comp (ref "R50")
      (value "4.7K 0402 1%")
      (footprint "R0402")
      (description "Resistor")
      (fields (field (name "MANUFACTURER_PART_NUMBER") "CR0402"))
      (libsource (lib "Compilation") (part "R0402"))
    )
    (comp (ref "R51")
      (value "4.7K 0402 1%")
      (footprint "R0402")
      (description "Resistor")
      (fields (field (name "MANUFACTURER_PART_NUMBER") "CR0402"))
      (libsource (lib "Compilation") (part "R0402"))
    )
    (comp (ref "R52")
      (value "120R 0402 1%")
      (footprint "R0402")
      (description "Resistor")
      (fields (field (name "MANUFACTURER_PART_NUMBER") "CR0402"))
      (libsource (lib "") (part "R0402_3"))
    )
    (comp (ref "R53")
      (value "4.7K 0402 1%")
      (footprint "R0402")
      (description "Resistor")
      (fields (field (name "MANUFACTURER_PART_NUMBER") "CR0402"))
      (libsource (lib "") (part "R0402_1"))
    )
    (comp (ref "R54")
      (value "1K 0402 1%")
      (footprint "R0402")
      (description "Resistor")
      (fields (field (name "MANUFACTURER_PART_NUMBER") "CR0402"))
      (libsource (lib "") (part "R0402_1"))
    )
    (comp (ref "R55")
      (value "1K 0402 1%")
      (footprint "R0402")
      (description "Resistor")
      (fields (field (name "MANUFACTURER_PART_NUMBER") "CR0402"))
      (libsource (lib "") (part "R0402_1"))
    )
    (comp (ref "R56")
      (value "10K 0402 1%")
      (footprint "R0402")
      (description "Resistor")
      (fields (field (name "MANUFACTURER_PART_NUMBER") "CR0402"))
      (libsource (lib "") (part "R0402_3"))
    )
    (comp (ref "R57")
      (value "1K 0402 1%")
      (footprint "R0402")
      (description "Resistor")
      (fields (field (name "MANUFACTURER_PART_NUMBER") "CR0402"))
      (libsource (lib "") (part "R0402_1"))
    )
    (comp (ref "R58")
      (value "1K 0402 1%")
      (footprint "R0402")
      (description "Resistor")
      (fields (field (name "MANUFACTURER_PART_NUMBER") "CR0402"))
      (libsource (lib "") (part "R0402_1"))
    )
    (comp (ref "S1")
      (value "轻触开关(3*6*2.5)-2P")
      (footprint "轻触开关(3*6*2.5)-2P")
      (description "Switch")
      (libsource (lib "Compilation") (part "轻触开关(3*6*2.5)-2P"))
    )
    (comp (ref "S2")
      (value "轻触开关(3*6*2.5)-2P")
      (footprint "轻触开关(3*6*2.5)-2P")
      (description "Switch")
      (libsource (lib "Compilation") (part "轻触开关(3*6*2.5)-2P"))
    )
    (comp (ref "TP1")
      (value "TESTPOINT")
      (footprint "TESTPOINT")
      (description "TestPoint")
      (libsource (lib "Compilation") (part "TESTPOINT"))
    )
    (comp (ref "TP2")
      (value "TESTPOINT")
      (footprint "TESTPOINT")
      (description "TestPoint")
      (libsource (lib "Compilation") (part "TESTPOINT"))
    )
    (comp (ref "Y1")
      (value "XTAL 25MHz")
      (footprint "XTAL25MHz 3225")
      (description "Crystal or Oscillator")
      (fields
        (field (name "MANUFACTURER_PART_NUMBER") "ABM8AIG-25.000MHZ-12-2Z-T3")
        (field (name "MOUSER PART NUMBER") "815-M8AIG-25-12-2ZT3")
      )
      (libsource (lib "Compilation") (part "XTAL 25MHz"))
    )
    (comp (ref "Z1")
      (value "BZX584C9V1")
      (footprint "BZX584C9V1")
      (description "Zener Diode")
      (fields
        (field (name "MANUFACTURER_PART_NUMBER") "BZX584C9V1-G3-08")
        (field (name "MOUSER PART NUMBER") "78-BZX584C9V1-G3-08")
      )
      (libsource (lib "Compilation") (part "BZX584C9V1"))
    )
    (comp (ref "Z2")
      (value "MMSZ5255")
      (footprint "MMSZ5255")
      (description "Zener Diode")
      (fields
        (field (name "MANUFACTURER_PART_NUMBER") "MMSZ5255BT1G")
        (field (name "MOUSER PART NUMBER") "863-MMSZ5255BT1G")
      )
      (libsource (lib "Compilation") (part "MMSZ5255"))
    )
    (comp (ref "Z3")
      (value "BZX584C9V1")
      (footprint "BZX584C9V1")
      (description "Zener Diode")
      (fields
        (field (name "MANUFACTURER_PART_NUMBER") "BZX584C9V1-G3-08")
        (field (name "MOUSER PART NUMBER") "78-BZX584C9V1-G3-08")
      )
      (libsource (lib "Compilation") (part "BZX584C9V1"))
    )
    (comp (ref "Z4")
      (value "BZX584C9V1")
      (footprint "BZX584C9V1")
      (description "Zener Diode")
      (fields
        (field (name "MANUFACTURER_PART_NUMBER") "BZX584C9V1-G3-08")
        (field (name "MOUSER PART NUMBER") "78-BZX584C9V1-G3-08")
      )
      (libsource (lib "Compilation") (part "BZX584C9V1"))
    )
  )
  (nets
    (net (code "1") (name "/BAT-") (class "Default")
      (node (ref "C8") (pin "2") (pinfunction "2_2") (pintype "passive"))
      (node (ref "C9") (pin "1") (pinfunction "1_1") (pintype "passive"))
      (node (ref "D1") (pin "1") (pinfunction "1_1") (pintype "passive"))
      (node (ref "IC2") (pin "12") (pinfunction "GND_12") (pintype "passive"))
      (node (ref "IC2") (pin "13") (pinfunction "GPIO4_13") (pintype "passive"))
      (node (ref "IC2") (pin "14") (pinfunction "GPIO2_14") (pintype "passive"))
      (node (ref "IC2") (pin "3") (pinfunction "GPIO1_3") (pintype "passive"))
      (node (ref "IC2") (pin "4") (pinfunction "GPIO3_4") (pintype "passive"))
      (node (ref "IC2") (pin "5") (pinfunction "ADR1_5") (pintype "passive"))
      (node (ref "IC2") (pin "6") (pinfunction "ADR0_6") (pintype "passive"))
      (node (ref "J1") (pin "2") (pinfunction "-_2") (pintype "passive"))
      (node (ref "MOS2") (pin "5") (pinfunction "D_5") (pintype "passive"))
      (node (ref "MOS2") (pin "6") (pinfunction "D_6") (pintype "passive"))
      (node (ref "MOS2") (pin "7") (pinfunction "D_7") (pintype "passive"))
      (node (ref "MOS2") (pin "8") (pinfunction "D_8") (pintype "passive"))
      (node (ref "MOS2") (pin "9") (pinfunction "D_9") (pintype "passive"))
      (node (ref "Z2") (pin "2") (pinfunction "A_2") (pintype "passive"))
    )
    (net (code "2") (name "/CAN1_H") (class "Default")
      (node (ref "IC5") (pin "7") (pinfunction "CANH_7") (pintype "passive"))
      (node (ref "J10") (pin "2") (pinfunction "2_2") (pintype "passive"))
      (node (ref "J11") (pin "2") (pinfunction "2_2") (pintype "passive"))
      (node (ref "J16") (pin "2") (pinfunction "2_2") (pintype "passive"))
      (node (ref "J17") (pin "2") (pinfunction "2_2") (pintype "passive"))
      (node (ref "J18") (pin "2") (pinfunction "2_2") (pintype "passive"))
      (node (ref "R43") (pin "2") (pinfunction "2_2") (pintype "passive"))
    )
    (net (code "3") (name "/CAN1_L") (class "Default")
      (node (ref "IC5") (pin "6") (pinfunction "CANL_6") (pintype "passive"))
      (node (ref "J10") (pin "1") (pinfunction "1_1") (pintype "passive"))
      (node (ref "J11") (pin "1") (pinfunction "1_1") (pintype "passive"))
      (node (ref "J16") (pin "1") (pinfunction "1_1") (pintype "passive"))
      (node (ref "J17") (pin "1") (pinfunction "1_1") (pintype "passive"))
      (node (ref "J18") (pin "1") (pinfunction "1_1") (pintype "passive"))
      (node (ref "R43") (pin "1") (pinfunction "1_1") (pintype "passive"))
    )
    (net (code "4") (name "/CAN1_RX(PA11)") (class "Default")
      (node (ref "IC5") (pin "4") (pinfunction "RXD_4") (pintype "passive"))
      (node (ref "IC7") (pin "C10") (pinfunction "PA11_C10") (pintype "passive"))
    )
    (net (code "5") (name "/CAN1_TX(PA12)") (class "Default")
      (node (ref "IC5") (pin "1") (pinfunction "TXD_1") (pintype "passive"))
      (node (ref "IC7") (pin "B10") (pinfunction "PA12_B10") (pintype "passive"))
    )
    (net (code "6") (name "/CAN2_H") (class "Default")
      (node (ref "IC6") (pin "7") (pinfunction "CANH_7") (pintype "passive"))
      (node (ref "J15") (pin "2") (pinfunction "2_2") (pintype "passive"))
      (node (ref "J22") (pin "2") (pinfunction "2_2") (pintype "passive"))
      (node (ref "J27") (pin "2") (pinfunction "2_2") (pintype "passive"))
      (node (ref "R49") (pin "2") (pinfunction "2_2") (pintype "passive"))
    )
    (net (code "7") (name "/CAN2_L") (class "Default")
      (node (ref "IC6") (pin "6") (pinfunction "CANL_6") (pintype "passive"))
      (node (ref "J15") (pin "1") (pinfunction "1_1") (pintype "passive"))
      (node (ref "J22") (pin "1") (pinfunction "1_1") (pintype "passive"))
      (node (ref "J27") (pin "1") (pinfunction "1_1") (pintype "passive"))
      (node (ref "R49") (pin "1") (pinfunction "1_1") (pintype "passive"))
    )
    (net (code "8") (name "/CAN2_RX(PB12)") (class "Default")
      (node (ref "IC6") (pin "4") (pinfunction "RXD_4") (pintype "passive"))
      (node (ref "IC7") (pin "K8") (pinfunction "PB12_K8") (pintype "passive"))
    )
    (net (code "9") (name "/CAN2_TX(PB13)") (class "Default")
      (node (ref "IC6") (pin "1") (pinfunction "TXD_1") (pintype "passive"))
      (node (ref "IC7") (pin "J8") (pinfunction "PB13_J8") (pintype "passive"))
    )
    (net (code "10") (name "/CAN3_H") (class "Default")
      (node (ref "IC8") (pin "7") (pinfunction "CANH_7") (pintype "passive"))
      (node (ref "J23") (pin "2") (pinfunction "2_2") (pintype "passive"))
      (node (ref "J28") (pin "2") (pinfunction "2_2") (pintype "passive"))
      (node (ref "R52") (pin "2") (pinfunction "2_2") (pintype "passive"))
    )
    (net (code "11") (name "/CAN3_L") (class "Default")
      (node (ref "IC8") (pin "6") (pinfunction "CANL_6") (pintype "passive"))
      (node (ref "J23") (pin "1") (pinfunction "1_1") (pintype "passive"))
      (node (ref "J28") (pin "1") (pinfunction "1_1") (pintype "passive"))
      (node (ref "R52") (pin "1") (pinfunction "1_1") (pintype "passive"))
    )
    (net (code "12") (name "/CAN3_RX(PB3)") (class "Default")
      (node (ref "IC7") (pin "A7") (pinfunction "PB3_A7") (pintype "passive"))
      (node (ref "IC8") (pin "4") (pinfunction "RXD_4") (pintype "passive"))
    )
    (net (code "13") (name "/CAN3_TX(PB4)") (class "Default")
      (node (ref "IC7") (pin "A6") (pinfunction "PB4_A6") (pintype "passive"))
      (node (ref "IC8") (pin "1") (pinfunction "TXD_1") (pintype "passive"))
    )
    (net (code "14") (name "/EXT_IO1(PC13)") (class "Default")
      (node (ref "IC7") (pin "A2") (pinfunction "PC13_A2") (pintype "passive"))
      (node (ref "J24") (pin "1") (pinfunction "1_1") (pintype "passive"))
    )
    (net (code "15") (name "/EXT_IO2(PE3)") (class "Default")
      (node (ref "IC7") (pin "B3") (pinfunction "PE3_B3") (pintype "passive"))
      (node (ref "J24") (pin "2") (pinfunction "2_2") (pintype "passive"))
    )
    (net (code "16") (name "/EXT_IO3(PE2)") (class "Default")
      (node (ref "IC7") (pin "A3") (pinfunction "PE2_A3") (pintype "passive"))
      (node (ref "J24") (pin "3") (pinfunction "3_3") (pintype "passive"))
    )
    (net (code "17") (name "/FEEDBACK2") (class "Default")
      (node (ref "IC4") (pin "5") (pinfunction "VSENSE_5") (pintype "passive"))
      (node (ref "R26") (pin "1") (pinfunction "1_1") (pintype "passive"))
      (node (ref "R31") (pin "2") (pinfunction "2_2") (pintype "passive"))
    )
    (net (code "18") (name "/I2C1_SCL(PB6)") (class "Default")
      (node (ref "IC7") (pin "B5") (pinfunction "PB6_B5") (pintype "passive"))
      (node (ref "J14") (pin "1") (pinfunction "1_1") (pintype "passive"))
      (node (ref "R44") (pin "1") (pinfunction "1_1") (pintype "passive"))
    )
    (net (code "19") (name "/I2C1_SDA(PB7)") (class "Default")
      (node (ref "IC7") (pin "A5") (pinfunction "PB7_A5") (pintype "passive"))
      (node (ref "J14") (pin "2") (pinfunction "2_2") (pintype "passive"))
      (node (ref "R47") (pin "1") (pinfunction "1_1") (pintype "passive"))
    )
    (net (code "20") (name "/I2C4_SCL(PD12)") (class "Default")
      (node (ref "IC2") (pin "9") (pinfunction "SCL_9") (pintype "passive"))
      (node (ref "IC7") (pin "K10") (pinfunction "PD12_K10") (pintype "passive"))
      (node (ref "R38") (pin "1") (pinfunction "1_1") (pintype "passive"))
    )
    (net (code "21") (name "/I2C4_SDA(PD13)") (class "Default")
      (node (ref "IC2") (pin "10") (pinfunction "SDAI_10") (pintype "passive"))
      (node (ref "IC2") (pin "11") (pinfunction "SDAO_11") (pintype "passive"))
      (node (ref "IC7") (pin "J10") (pinfunction "PD13_J10") (pintype "passive"))
      (node (ref "R41") (pin "1") (pinfunction "1_1") (pintype "passive"))
    )
    (net (code "22") (name "/LED1(PD4)") (class "Default")
      (node (ref "IC7") (pin "D7") (pinfunction "PD4_D7") (pintype "passive"))
      (node (ref "LED4") (pin "2") (pinfunction "2_2") (pintype "passive"))
    )
    (net (code "23") (name "/LED2(PA9)") (class "Default")
      (node (ref "IC7") (pin "C9") (pinfunction "PA9_C9") (pintype "passive"))
      (node (ref "LED5") (pin "2") (pinfunction "2_2") (pintype "passive"))
    )
    (net (code "24") (name "/LED4(PA10)") (class "Default")
      (node (ref "IC7") (pin "D10") (pinfunction "PA10_D10") (pintype "passive"))
      (node (ref "LED6") (pin "2") (pinfunction "2_2") (pintype "passive"))
    )
    (net (code "25") (name "/LED4(PD0)") (class "Default")
      (node (ref "IC7") (pin "D8") (pinfunction "PD0_D8") (pintype "passive"))
      (node (ref "LED7") (pin "2") (pinfunction "2_2") (pintype "passive"))
    )
    (net (code "26") (name "/OUT1(PD10)") (class "Default")
      (node (ref "C24") (pin "2") (pinfunction "2_2") (pintype "passive"))
      (node (ref "IC7") (pin "H9") (pinfunction "PD10_H9") (pintype "passive"))
      (node (ref "R28") (pin "2") (pinfunction "2_2") (pintype "passive"))
    )
    (net (code "27") (name "/OUT2(PA7)") (class "Default")
      (node (ref "C25") (pin "2") (pinfunction "2_2") (pintype "passive"))
      (node (ref "IC7") (pin "K3") (pinfunction "PA7_K3") (pintype "passive"))
      (node (ref "R29") (pin "2") (pinfunction "2_2") (pintype "passive"))
    )
    (net (code "28") (name "/PWM1(PB0)") (class "Default")
      (node (ref "IC7") (pin "J4") (pinfunction "PB0_J4") (pintype "passive"))
      (node (ref "L4") (pin "1") (pinfunction "1_1") (pintype "passive"))
    )
    (net (code "29") (name "/PWM2(PB1)") (class "Default")
      (node (ref "IC7") (pin "K4") (pinfunction "PB1_K4") (pintype "passive"))
      (node (ref "L5") (pin "1") (pinfunction "1_1") (pintype "passive"))
    )
    (net (code "30") (name "/PWM3(PE8)") (class "Default")
      (node (ref "IC7") (pin "J5") (pinfunction "PE8_J5") (pintype "passive"))
      (node (ref "L6") (pin "1") (pinfunction "1_1") (pintype "passive"))
    )
    (net (code "31") (name "/PWM4(PE9)") (class "Default")
      (node (ref "IC7") (pin "K5") (pinfunction "PE9_K5") (pintype "passive"))
      (node (ref "L7") (pin "1") (pinfunction "1_1") (pintype "passive"))
    )
    (net (code "32") (name "/PWM5(PE12)") (class "Default")
      (node (ref "IC7") (pin "J6") (pinfunction "PE12_J6") (pintype "passive"))
      (node (ref "L8") (pin "1") (pinfunction "1_1") (pintype "passive"))
    )
    (net (code "33") (name "/PWM6(PE13)") (class "Default")
      (node (ref "IC7") (pin "K6") (pinfunction "PE13_K6") (pintype "passive"))
      (node (ref "L9") (pin "1") (pinfunction "1_1") (pintype "passive"))
    )
    (net (code "34") (name "/PWM7(PB10)") (class "Default")
      (node (ref "IC7") (pin "J7") (pinfunction "PB10_J7") (pintype "passive"))
      (node (ref "L10") (pin "1") (pinfunction "1_1") (pintype "passive"))
    )
    (net (code "35") (name "/PWM8(PB11)") (class "Default")
      (node (ref "IC7") (pin "K7") (pinfunction "PB11_K7") (pintype "passive"))
      (node (ref "L11") (pin "1") (pinfunction "1_1") (pintype "passive"))
    )
    (net (code "36") (name "/SDMMC1_CK(PC12)") (class "Default")
      (node (ref "IC7") (pin "C8") (pinfunction "PC12_C8") (pintype "passive"))
      (node (ref "J8") (pin "5") (pinfunction "CLK_5") (pintype "passive"))
    )
    (net (code "37") (name "/SDMMC1_CMD(PD2)") (class "Default")
      (node (ref "IC7") (pin "B7") (pinfunction "PD2_B7") (pintype "passive"))
      (node (ref "J8") (pin "3") (pinfunction "CMD_3") (pintype "passive"))
      (node (ref "R46") (pin "1") (pinfunction "1_1") (pintype "passive"))
    )
    (net (code "38") (name "/SDMMC1_D0(PC8)") (class "Default")
      (node (ref "IC7") (pin "F9") (pinfunction "PC8_F9") (pintype "passive"))
      (node (ref "J8") (pin "7") (pinfunction "DAT0_7") (pintype "passive"))
      (node (ref "R45") (pin "1") (pinfunction "1_1") (pintype "passive"))
    )
    (net (code "39") (name "/SDMMC1_D1(PC9)") (class "Default")
      (node (ref "IC7") (pin "E9") (pinfunction "PC9_E9") (pintype "passive"))
      (node (ref "J8") (pin "8") (pinfunction "DAT1_8") (pintype "passive"))
      (node (ref "R48") (pin "1") (pinfunction "1_1") (pintype "passive"))
    )
    (net (code "40") (name "/SDMMC1_D2(PC10)") (class "Default")
      (node (ref "IC7") (pin "B9") (pinfunction "PC10_B9") (pintype "passive"))
      (node (ref "J8") (pin "1") (pinfunction "DAT2_1") (pintype "passive"))
      (node (ref "R39") (pin "1") (pinfunction "1_1") (pintype "passive"))
    )
    (net (code "41") (name "/SDMMC1_D3(PC11)") (class "Default")
      (node (ref "IC7") (pin "B8") (pinfunction "PC11_B8") (pintype "passive"))
      (node (ref "J8") (pin "2") (pinfunction "CD/DAT3_2") (pintype "passive"))
      (node (ref "R42") (pin "1") (pinfunction "1_1") (pintype "passive"))
    )
    (net (code "42") (name "/SWCLK(PA14)") (class "Default")
      (node (ref "IC7") (pin "A9") (pinfunction "PA14_A9") (pintype "passive"))
      (node (ref "J6") (pin "A6") (pinfunction "DP1_A6") (pintype "passive"))
      (node (ref "J6") (pin "B6") (pinfunction "DP2_B6") (pintype "passive"))
      (node (ref "R40") (pin "1") (pinfunction "1_1") (pintype "passive"))
    )
    (net (code "43") (name "/SWDIO(PA13)") (class "Default")
      (node (ref "IC7") (pin "A10") (pinfunction "PA13_A10") (pintype "passive"))
      (node (ref "J6") (pin "A7") (pinfunction "DN1_A7") (pintype "passive"))
      (node (ref "J6") (pin "B7") (pinfunction "DN2_B7") (pintype "passive"))
      (node (ref "R37") (pin "1") (pinfunction "1_1") (pintype "passive"))
    )
    (net (code "44") (name "/TIM9_CH2(PE6)") (class "Default")
      (node (ref "BUZ1") (pin "3") (pinfunction "3_3") (pintype "passive"))
      (node (ref "IC7") (pin "E3") (pinfunction "PE6_E3") (pintype "passive"))
    )
    (net (code "45") (name "/UART4_RX(PA1)") (class "Default")
      (node (ref "IC7") (pin "H2") (pinfunction "PA1_H2") (pintype "passive"))
      (node (ref "J13") (pin "1") (pinfunction "1_1") (pintype "passive"))
    )
    (net (code "46") (name "/UART4_TX(PA0)") (class "Default")
      (node (ref "IC7") (pin "G2") (pinfunction "PA0_G2") (pintype "passive"))
      (node (ref "J13") (pin "2") (pinfunction "2_2") (pintype "passive"))
    )
    (net (code "47") (name "/UART5_RX(PB8)") (class "Default")
      (node (ref "IC7") (pin "B4") (pinfunction "PB8_B4") (pintype "passive"))
      (node (ref "J19") (pin "1") (pinfunction "1_1") (pintype "passive"))
    )
    (net (code "48") (name "/UART5_TX(PB9)") (class "Default")
      (node (ref "IC7") (pin "A4") (pinfunction "PB9_A4") (pintype "passive"))
      (node (ref "J19") (pin "2") (pinfunction "2_2") (pintype "passive"))
    )
    (net (code "49") (name "/UART7_RX(PA8)") (class "Default")
      (node (ref "IC7") (pin "D9") (pinfunction "PA8_D9") (pintype "passive"))
      (node (ref "J6") (pin "A5") (pinfunction "CC1_A5") (pintype "passive"))
      (node (ref "J6") (pin "B5") (pinfunction "CC2_B5") (pintype "passive"))
    )
    (net (code "50") (name "/UART7_TX(PA15)") (class "Default")
      (node (ref "IC7") (pin "A8") (pinfunction "PA15_A8") (pintype "passive"))
      (node (ref "J6") (pin "A8") (pinfunction "SBU1_A8") (pintype "passive"))
      (node (ref "J6") (pin "B8") (pinfunction "SBU2_B8") (pintype "passive"))
    )
    (net (code "51") (name "/UART8_RX(PE0)") (class "Default")
      (node (ref "IC7") (pin "D4") (pinfunction "PE0_D4") (pintype "passive"))
      (node (ref "J12") (pin "1") (pinfunction "1_1") (pintype "passive"))
    )
    (net (code "52") (name "/UART8_TX(PE1)") (class "Default")
      (node (ref "IC7") (pin "C4") (pinfunction "PE1_C4") (pintype "passive"))
      (node (ref "J12") (pin "2") (pinfunction "2_2") (pintype "passive"))
    )
    (net (code "53") (name "/USART1_RX(PB15)") (class "Default")
      (node (ref "IC7") (pin "G10") (pinfunction "PB15_G10") (pintype "passive"))
      (node (ref "J26") (pin "1") (pinfunction "1_1") (pintype "passive"))
    )
    (net (code "54") (name "/USART1_TX(PB14)") (class "Default")
      (node (ref "IC7") (pin "H10") (pinfunction "PB14_H10") (pintype "passive"))
      (node (ref "J26") (pin "2") (pinfunction "2_2") (pintype "passive"))
    )
    (net (code "55") (name "/USART2_RX(PA3)") (class "Default")
      (node (ref "IC7") (pin "K2") (pinfunction "PA3_K2") (pintype "passive"))
      (node (ref "J25") (pin "1") (pinfunction "1_1") (pintype "passive"))
      (node (ref "Q4") (pin "3") (pinfunction "C_3") (pintype "passive"))
      (node (ref "R50") (pin "1") (pinfunction "1_1") (pintype "passive"))
    )
    (net (code "56") (name "/USART2_TX(PA2)") (class "Default")
      (node (ref "IC7") (pin "J2") (pinfunction "PA2_J2") (pintype "passive"))
      (node (ref "J25") (pin "2") (pinfunction "2_2") (pintype "passive"))
    )
    (net (code "57") (name "/USART3_RX(PD9)") (class "Default")
      (node (ref "IC7") (pin "J9") (pinfunction "PD9_J9") (pintype "passive"))
      (node (ref "J21") (pin "1") (pinfunction "1_1") (pintype "passive"))
    )
    (net (code "58") (name "/USART3_TX(PD8)") (class "Default")
      (node (ref "IC7") (pin "K9") (pinfunction "PD8_K9") (pintype "passive"))
      (node (ref "J21") (pin "2") (pinfunction "2_2") (pintype "passive"))
    )
    (net (code "59") (name "/USART6_RX(PC7)") (class "Default")
      (node (ref "IC7") (pin "E10") (pinfunction "PC7_E10") (pintype "passive"))
      (node (ref "J20") (pin "1") (pinfunction "1_1") (pintype "passive"))
    )
    (net (code "60") (name "/USART6_TX(PC6)") (class "Default")
      (node (ref "IC7") (pin "F10") (pinfunction "PC6_F10") (pintype "passive"))
      (node (ref "J20") (pin "2") (pinfunction "2_2") (pintype "passive"))
    )
    (net (code "61") (name "/USER_KEY(PC0)") (class "Default")
      (node (ref "C27") (pin "2") (pinfunction "2_2") (pintype "passive"))
      (node (ref "IC7") (pin "F1") (pinfunction "PC0_F1") (pintype "passive"))
      (node (ref "S1") (pin "2") (pinfunction "2_2") (pintype "passive"))
    )
    (net (code "62") (name "GND") (class "Default")
      (node (ref "C26") (pin "1") (pinfunction "1_1") (pintype "passive"))
      (node (ref "C27") (pin "1") (pinfunction "1_1") (pintype "passive"))
      (node (ref "C28") (pin "1") (pinfunction "1_1") (pintype "passive"))
      (node (ref "C29") (pin "1") (pinfunction "1_1") (pintype "passive"))
      (node (ref "C30") (pin "2") (pinfunction "2_2") (pintype "passive"))
      (node (ref "C31") (pin "1") (pinfunction "1_1") (pintype "passive"))
      (node (ref "C32") (pin "1") (pinfunction "1_1") (pintype "passive"))
      (node (ref "C33") (pin "1") (pinfunction "1_1") (pintype "passive"))
      (node (ref "C34") (pin "1") (pinfunction "1_1") (pintype "passive"))
      (node (ref "C35") (pin "1") (pinfunction "1_1") (pintype "passive"))
      (node (ref "C36") (pin "1") (pinfunction "1_1") (pintype "passive"))
      (node (ref "C37") (pin "1") (pinfunction "1_1") (pintype "passive"))
      (node (ref "C38") (pin "1") (pinfunction "1_1") (pintype "passive"))
      (node (ref "C39") (pin "1") (pinfunction "1_1") (pintype "passive"))
      (node (ref "C40") (pin "1") (pinfunction "1_1") (pintype "passive"))
      (node (ref "C41") (pin "1") (pinfunction "1_1") (pintype "passive"))
      (node (ref "IC5") (pin "2") (pinfunction "GND_2") (pintype "passive"))
      (node (ref "IC5") (pin "8") (pinfunction "STB_8") (pintype "passive"))
      (node (ref "IC6") (pin "2") (pinfunction "GND_2") (pintype "passive"))
      (node (ref "IC6") (pin "8") (pinfunction "STB_8") (pintype "passive"))
      (node (ref "IC7") (pin "C2") (pinfunction "VSS_1_C2") (pintype "passive"))
      (node (ref "IC7") (pin "E4") (pinfunction "VSS_2_E4") (pintype "passive"))
      (node (ref "IC7") (pin "E5") (pinfunction "VSS_3_E5") (pintype "passive"))
      (node (ref "IC7") (pin "E6") (pinfunction "BYPASS-REG_E6") (pintype "passive"))
      (node (ref "IC7") (pin "G1") (pinfunction "VSSA_G1") (pintype "passive"))
      (node (ref "IC7") (pin "J1") (pinfunction "VSS_4_J1") (pintype "passive"))
      (node (ref "IC8") (pin "2") (pinfunction "GND_2") (pintype "passive"))
      (node (ref "IC8") (pin "8") (pinfunction "STB_8") (pintype "passive"))
      (node (ref "IC9") (pin "2") (pinfunction "GND_2") (pintype "passive"))
      (node (ref "J12") (pin "3") (pinfunction "3_3") (pintype "passive"))
      (node (ref "J13") (pin "3") (pinfunction "3_3") (pintype "passive"))
      (node (ref "J14") (pin "3") (pinfunction "3_3") (pintype "passive"))
      (node (ref "J19") (pin "3") (pinfunction "3_3") (pintype "passive"))
      (node (ref "J20") (pin "3") (pinfunction "3_3") (pintype "passive"))
      (node (ref "J21") (pin "3") (pinfunction "3_3") (pintype "passive"))
      (node (ref "J24") (pin "4") (pinfunction "4_4") (pintype "passive"))
      (node (ref "J25") (pin "3") (pinfunction "3_3") (pintype "passive"))
      (node (ref "J26") (pin "3") (pinfunction "3_3") (pintype "passive"))
      (node (ref "J6") (pin "A1") (pinfunction "GND_1_A1") (pintype "passive"))
      (node (ref "J6") (pin "A12") (pinfunction "GND_2_A12") (pintype "passive"))
      (node (ref "J6") (pin "B1") (pinfunction "GND_3_B1") (pintype "passive"))
      (node (ref "J6") (pin "B12") (pinfunction "GND_4_B12") (pintype "passive"))
      (node (ref "J6") (pin "MP1") (pinfunction "MP1_MP1") (pintype "passive"))
      (node (ref "J6") (pin "MP2") (pinfunction "MP2_MP2") (pintype "passive"))
      (node (ref "J6") (pin "MP3") (pinfunction "MP3_MP3") (pintype "passive"))
      (node (ref "J6") (pin "MP4") (pinfunction "MP4_MP4") (pintype "passive"))
      (node (ref "J8") (pin "6") (pinfunction "VSS_6") (pintype "passive"))
      (node (ref "J8") (pin "G1") (pinfunction "GND_1_G1") (pintype "passive"))
      (node (ref "J8") (pin "G2") (pinfunction "GND_2_G2") (pintype "passive"))
      (node (ref "J8") (pin "G3") (pinfunction "GND_3_G3") (pintype "passive"))
      (node (ref "J8") (pin "G4") (pinfunction "GND_4_G4") (pintype "passive"))
      (node (ref "J9") (pin "1") (pinfunction "1_1") (pintype "passive"))
      (node (ref "Q4") (pin "2") (pinfunction "E_2") (pintype "passive"))
      (node (ref "R35") (pin "2") (pinfunction "2_2") (pintype "passive"))
      (node (ref "R36") (pin "2") (pinfunction "2_2") (pintype "passive"))
      (node (ref "R56") (pin "1") (pinfunction "1_1") (pintype "passive"))
      (node (ref "S2") (pin "2") (pinfunction "2_2") (pintype "passive"))
      (node (ref "Y1") (pin "2") (pinfunction "2_2") (pintype "passive"))
      (node (ref "Y1") (pin "4") (pinfunction "4_4") (pintype "passive"))
    )
    (net (code "63") (name "Net-(C7-Pad2)") (class "Default")
      (node (ref "C7") (pin "2") (pinfunction "2_2") (pintype "passive"))
      (node (ref "R8") (pin "2") (pinfunction "2_2") (pintype "passive"))
    )
    (net (code "64") (name "Net-(C9-Pad2)") (class "Default")
      (node (ref "C9") (pin "2") (pinfunction "2_2") (pintype "passive"))
      (node (ref "R2") (pin "1") (pinfunction "1_1") (pintype "passive"))
    )
    (net (code "65") (name "Net-(C10-Pad2)") (class "Default")
      (node (ref "C10") (pin "2") (pinfunction "2_2") (pintype "passive"))
      (node (ref "R5") (pin "1") (pinfunction "1_1") (pintype "passive"))
    )
    (net (code "66") (name "Net-(C22-Pad1)") (class "Default")
      (node (ref "C22") (pin "1") (pinfunction "1_1") (pintype "passive"))
      (node (ref "R30") (pin "2") (pinfunction "2_2") (pintype "passive"))
    )
    (net (code "67") (name "Net-(D2-K)") (class "Default")
      (node (ref "C12") (pin "2") (pinfunction "2_2") (pintype "passive"))
      (node (ref "D2") (pin "1") (pinfunction "K_1") (pintype "passive"))
      (node (ref "IC4") (pin "8") (pinfunction "PH_8") (pintype "passive"))
      (node (ref "L3") (pin "1") (pinfunction "1_1") (pintype "passive"))
    )
    (net (code "68") (name "Net-(IC1-FB1)") (class "Default")
      (node (ref "IC1") (pin "28") (pinfunction "FB1_28") (pintype "passive"))
      (node (ref "IC1") (pin "31") (pinfunction "FB2_31") (pintype "passive"))
      (node (ref "P1") (pin "4") (pinfunction "4_4") (pintype "passive"))
      (node (ref "P1") (pin "5") (pinfunction "5_5") (pintype "passive"))
      (node (ref "P1") (pin "6") (pinfunction "6_6") (pintype "passive"))
      (node (ref "R10") (pin "1") (pinfunction "1_1") (pintype "passive"))
      (node (ref "R6") (pin "2") (pinfunction "2_2") (pintype "passive"))
    )
    (net (code "69") (name "Net-(IC1-PG1)") (class "Default")
      (node (ref "IC1") (pin "14") (pinfunction "PG1_14") (pintype "passive"))
      (node (ref "IC1") (pin "15") (pinfunction "PG2_15") (pintype "passive"))
      (node (ref "R16") (pin "1") (pinfunction "1_1") (pintype "passive"))
    )
    (net (code "70") (name "Net-(IC1-RT)") (class "Default")
      (node (ref "IC1") (pin "1") (pinfunction "RT_1") (pintype "passive"))
      (node (ref "R11") (pin "2") (pinfunction "2_2") (pintype "passive"))
    )
    (net (code "71") (name "Net-(IC1-SS1)") (class "Default")
      (node (ref "C11") (pin "1") (pinfunction "1_1") (pintype "passive"))
      (node (ref "IC1") (pin "29") (pinfunction "SS1_29") (pintype "passive"))
      (node (ref "IC1") (pin "30") (pinfunction "SS2_30") (pintype "passive"))
    )
    (net (code "72") (name "Net-(IC1-SW1_1)") (class "Default")
      (node (ref "IC1") (pin "22") (pinfunction "SW1_1_22") (pintype "passive"))
      (node (ref "IC1") (pin "23") (pinfunction "SW1_2_23") (pintype "passive"))
      (node (ref "L1") (pin "1") (pinfunction "1_1") (pintype "passive"))
    )
    (net (code "73") (name "Net-(IC1-SW2_1)") (class "Default")
      (node (ref "IC1") (pin "19") (pinfunction "SW2_1_19") (pintype "passive"))
      (node (ref "IC1") (pin "20") (pinfunction "SW2_2_20") (pintype "passive"))
      (node (ref "L2") (pin "1") (pinfunction "1_1") (pintype "passive"))
    )
    (net (code "74") (name "Net-(IC1-VC1)") (class "Default")
      (node (ref "IC1") (pin "27") (pinfunction "VC1_27") (pintype "passive"))
      (node (ref "IC1") (pin "32") (pinfunction "VC2_32") (pintype "passive"))
      (node (ref "R8") (pin "1") (pinfunction "1_1") (pintype "passive"))
    )
    (net (code "75") (name "Net-(IC1-VCC)") (class "Default")
      (node (ref "C5") (pin "2") (pinfunction "2_2") (pintype "passive"))
      (node (ref "IC1") (pin "25") (pinfunction "VCC_25") (pintype "passive"))
    )
    (net (code "76") (name "Net-(IC2-INTVCC)") (class "Default")
      (node (ref "C8") (pin "1") (pinfunction "1_1") (pintype "passive"))
      (node (ref "IC2") (pin "7") (pinfunction "INTVCC_7") (pintype "passive"))
    )
    (net (code "77") (name "Net-(IC2-SENSE1+)") (class "Default")
      (node (ref "D1") (pin "2") (pinfunction "2_2") (pintype "passive"))
      (node (ref "IC2") (pin "15") (pinfunction "SENSE2+_15") (pintype "passive"))
      (node (ref "IC2") (pin "2") (pinfunction "SENSE1+_2") (pintype "passive"))
      (node (ref "IC2") (pin "8") (pinfunction "VDD_8") (pintype "passive"))
      (node (ref "J1") (pin "1") (pinfunction "+_1") (pintype "passive"))
      (node (ref "R1") (pin "1") (pinfunction "1_1") (pintype "passive"))
    )
    (net (code "78") (name "Net-(IC2-SENSE1-)") (class "Default")
      (node (ref "IC2") (pin "1") (pinfunction "SENSE1-_1") (pintype "passive"))
      (node (ref "IC2") (pin "16") (pinfunction "SENSE2-_16") (pintype "passive"))
      (node (ref "MOS1") (pin "1") (pinfunction "1_1") (pintype "passive"))
      (node (ref "MOS1") (pin "2") (pinfunction "2_2") (pintype "passive"))
      (node (ref "MOS1") (pin "3") (pinfunction "3_3") (pintype "passive"))
      (node (ref "Q1") (pin "2") (pinfunction "E_2") (pintype "passive"))
      (node (ref "R1") (pin "2") (pinfunction "2_2") (pintype "passive"))
      (node (ref "R2") (pin "2") (pinfunction "2_2") (pintype "passive"))
      (node (ref "R3") (pin "2") (pinfunction "2_2") (pintype "passive"))
      (node (ref "R4") (pin "2") (pinfunction "2_2") (pintype "passive"))
    )
    (net (code "79") (name "Net-(IC4-BOOT)") (class "Default")
      (node (ref "C12") (pin "1") (pinfunction "1_1") (pintype "passive"))
      (node (ref "IC4") (pin "1") (pinfunction "BOOT_1") (pintype "passive"))
    )
    (net (code "80") (name "Net-(IC4-COMP)") (class "Default")
      (node (ref "C21") (pin "2") (pinfunction "2_2") (pintype "passive"))
      (node (ref "C22") (pin "2") (pinfunction "2_2") (pintype "passive"))
      (node (ref "IC4") (pin "6") (pinfunction "COMP_6") (pintype "passive"))
    )
    (net (code "81") (name "Net-(IC4-EN)") (class "Default")
      (node (ref "IC4") (pin "3") (pinfunction "EN_3") (pintype "passive"))
      (node (ref "R27") (pin "1") (pinfunction "1_1") (pintype "passive"))
      (node (ref "R32") (pin "2") (pinfunction "2_2") (pintype "passive"))
    )
    (net (code "82") (name "Net-(IC4-SS)") (class "Default")
      (node (ref "C23") (pin "1") (pinfunction "1_1") (pintype "passive"))
      (node (ref "IC4") (pin "4") (pinfunction "SS_4") (pintype "passive"))
    )
    (net (code "83") (name "Net-(IC7A-BOOT0)") (class "Default")
      (node (ref "IC7") (pin "D5") (pinfunction "BOOT0_D5") (pintype "passive"))
      (node (ref "R56") (pin "2") (pinfunction "2_2") (pintype "passive"))
    )
    (net (code "84") (name "Net-(IC7A-NRST)") (class "Default")
      (node (ref "C32") (pin "2") (pinfunction "2_2") (pintype "passive"))
      (node (ref "IC7") (pin "E1") (pinfunction "NRST_E1") (pintype "passive"))
      (node (ref "R53") (pin "1") (pinfunction "1_1") (pintype "passive"))
      (node (ref "S2") (pin "1") (pinfunction "1_1") (pintype "passive"))
    )
    (net (code "85") (name "Net-(IC7A-PH0_OSC_IN)") (class "Default")
      (node (ref "C30") (pin "1") (pinfunction "1_1") (pintype "passive"))
      (node (ref "IC7") (pin "C1") (pinfunction "PH0_OSC_IN_C1") (pintype "passive"))
      (node (ref "Y1") (pin "1") (pinfunction "1_1") (pintype "passive"))
    )
    (net (code "86") (name "Net-(IC7A-PH1_OSC_OUT)") (class "Default")
      (node (ref "C31") (pin "2") (pinfunction "2_2") (pintype "passive"))
      (node (ref "IC7") (pin "D1") (pinfunction "PH1_OSC_OUT_D1") (pintype "passive"))
      (node (ref "Y1") (pin "3") (pinfunction "3_3") (pintype "passive"))
    )
    (net (code "87") (name "Net-(IC7A-VCAP_1)") (class "Default")
      (node (ref "C34") (pin "2") (pinfunction "2_2") (pintype "passive"))
      (node (ref "IC7") (pin "F8") (pinfunction "VCAP_1_F8") (pintype "passive"))
    )
    (net (code "88") (name "Net-(IC7A-VCAP_2)") (class "Default")
      (node (ref "C33") (pin "2") (pinfunction "2_2") (pintype "passive"))
      (node (ref "IC7") (pin "E7") (pinfunction "VCAP_2_E7") (pintype "passive"))
    )
    (net (code "89") (name "Net-(J7-Pad1)") (class "Default")
      (node (ref "J7") (pin "1") (pinfunction "1_1") (pintype "passive"))
      (node (ref "L4") (pin "2") (pinfunction "2_2") (pintype "passive"))
    )
    (net (code "90") (name "Net-(J7-Pad2)") (class "Default")
      (node (ref "J7") (pin "2") (pinfunction "2_2") (pintype "passive"))
      (node (ref "L5") (pin "2") (pinfunction "2_2") (pintype "passive"))
    )
    (net (code "91") (name "Net-(J7-Pad3)") (class "Default")
      (node (ref "J7") (pin "3") (pinfunction "3_3") (pintype "passive"))
      (node (ref "L6") (pin "2") (pinfunction "2_2") (pintype "passive"))
    )
    (net (code "92") (name "Net-(J7-Pad4)") (class "Default")
      (node (ref "J7") (pin "4") (pinfunction "4_4") (pintype "passive"))
      (node (ref "L7") (pin "2") (pinfunction "2_2") (pintype "passive"))
    )
    (net (code "93") (name "Net-(J7-Pad5)") (class "Default")
      (node (ref "J7") (pin "5") (pinfunction "5_5") (pintype "passive"))
      (node (ref "L8") (pin "2") (pinfunction "2_2") (pintype "passive"))
    )
    (net (code "94") (name "Net-(J7-Pad6)") (class "Default")
      (node (ref "J7") (pin "6") (pinfunction "6_6") (pintype "passive"))
      (node (ref "L9") (pin "2") (pinfunction "2_2") (pintype "passive"))
    )
    (net (code "95") (name "Net-(J7-Pad7)") (class "Default")
      (node (ref "J7") (pin "7") (pinfunction "7_7") (pintype "passive"))
      (node (ref "L10") (pin "2") (pinfunction "2_2") (pintype "passive"))
    )
    (net (code "96") (name "Net-(J7-Pad8)") (class "Default")
      (node (ref "J7") (pin "8") (pinfunction "8_8") (pintype "passive"))
      (node (ref "L11") (pin "2") (pinfunction "2_2") (pintype "passive"))
    )
    (net (code "97") (name "Net-(J9-Pad3)") (class "Default")
      (node (ref "J9") (pin "3") (pinfunction "3_3") (pintype "passive"))
      (node (ref "R51") (pin "1") (pinfunction "1_1") (pintype "passive"))
    )
    (net (code "98") (name "Net-(LED1-Pad1)") (class "Default")
      (node (ref "LED1") (pin "1") (pinfunction "1_1") (pintype "passive"))
      (node (ref "R20") (pin "2") (pinfunction "2_2") (pintype "passive"))
    )
    (net (code "99") (name "Net-(LED2-Pad1)") (class "Default")
      (node (ref "LED2") (pin "1") (pinfunction "1_1") (pintype "passive"))
      (node (ref "R22") (pin "2") (pinfunction "2_2") (pintype "passive"))
    )
    (net (code "100") (name "Net-(LED3-Pad1)") (class "Default")
      (node (ref "LED3") (pin "1") (pinfunction "1_1") (pintype "passive"))
      (node (ref "R23") (pin "2") (pinfunction "2_2") (pintype "passive"))
    )
    (net (code "101") (name "Net-(LED4-Pad1)") (class "Default")
      (node (ref "LED4") (pin "1") (pinfunction "1_1") (pintype "passive"))
      (node (ref "R54") (pin "2") (pinfunction "2_2") (pintype "passive"))
    )
    (net (code "102") (name "Net-(LED5-Pad1)") (class "Default")
      (node (ref "LED5") (pin "1") (pinfunction "1_1") (pintype "passive"))
      (node (ref "R55") (pin "2") (pinfunction "2_2") (pintype "passive"))
    )
    (net (code "103") (name "Net-(LED6-Pad1)") (class "Default")
      (node (ref "LED6") (pin "1") (pinfunction "1_1") (pintype "passive"))
      (node (ref "R57") (pin "2") (pinfunction "2_2") (pintype "passive"))
    )
    (net (code "104") (name "Net-(LED7-Pad1)") (class "Default")
      (node (ref "LED7") (pin "1") (pinfunction "1_1") (pintype "passive"))
      (node (ref "R58") (pin "2") (pinfunction "2_2") (pintype "passive"))
    )
    (net (code "105") (name "Net-(MOS1-Pad4)") (class "Default")
      (node (ref "MOS1") (pin "4") (pinfunction "4_4") (pintype "passive"))
      (node (ref "R9") (pin "2") (pinfunction "2_2") (pintype "passive"))
    )
    (net (code "106") (name "Net-(MOS2-G)") (class "Default")
      (node (ref "MOS2") (pin "4") (pinfunction "G_4") (pintype "passive"))
      (node (ref "R3") (pin "1") (pinfunction "1_1") (pintype "passive"))
      (node (ref "Z1") (pin "1") (pinfunction "1_1") (pintype "passive"))
    )
    (net (code "107") (name "Net-(MOS3-Pad4)") (class "Default")
      (node (ref "MOS3") (pin "4") (pinfunction "4_4") (pintype "passive"))
      (node (ref "R19") (pin "2") (pinfunction "2_2") (pintype "passive"))
      (node (ref "R24") (pin "1") (pinfunction "1_1") (pintype "passive"))
      (node (ref "Z3") (pin "2") (pinfunction "2_2") (pintype "passive"))
    )
    (net (code "108") (name "Net-(MOS4-Pad4)") (class "Default")
      (node (ref "MOS4") (pin "4") (pinfunction "4_4") (pintype "passive"))
      (node (ref "R21") (pin "2") (pinfunction "2_2") (pintype "passive"))
      (node (ref "R25") (pin "1") (pinfunction "1_1") (pintype "passive"))
      (node (ref "Z4") (pin "2") (pinfunction "2_2") (pintype "passive"))
    )
    (net (code "109") (name "Net-(P1-Pad1)") (class "Default")
      (node (ref "P1") (pin "1") (pinfunction "1_1") (pintype "passive"))
      (node (ref "R17") (pin "1") (pinfunction "1_1") (pintype "passive"))
    )
    (net (code "110") (name "Net-(P1-Pad2)") (class "Default")
      (node (ref "P1") (pin "2") (pinfunction "2_2") (pintype "passive"))
      (node (ref "R15") (pin "1") (pinfunction "1_1") (pintype "passive"))
    )
    (net (code "111") (name "Net-(P1-Pad3)") (class "Default")
      (node (ref "P1") (pin "3") (pinfunction "3_3") (pintype "passive"))
      (node (ref "R12") (pin "1") (pinfunction "1_1") (pintype "passive"))
    )
    (net (code "112") (name "Net-(Q1-B)") (class "Default")
      (node (ref "C6") (pin "2") (pinfunction "2_2") (pintype "passive"))
      (node (ref "Q1") (pin "1") (pinfunction "B_1") (pintype "passive"))
      (node (ref "R7") (pin "2") (pinfunction "2_2") (pintype "passive"))
    )
    (net (code "113") (name "Net-(Q1-C)") (class "Default")
      (node (ref "C6") (pin "1") (pinfunction "1_1") (pintype "passive"))
      (node (ref "Q1") (pin "3") (pinfunction "C_3") (pintype "passive"))
      (node (ref "R14") (pin "2") (pinfunction "2_2") (pintype "passive"))
      (node (ref "R9") (pin "1") (pinfunction "1_1") (pintype "passive"))
    )
    (net (code "114") (name "Net-(Q2-B)") (class "Default")
      (node (ref "Q2") (pin "1") (pinfunction "B_1") (pintype "passive"))
      (node (ref "R28") (pin "1") (pinfunction "1_1") (pintype "passive"))
      (node (ref "R33") (pin "1") (pinfunction "1_1") (pintype "passive"))
    )
    (net (code "115") (name "Net-(Q2-C)") (class "Default")
      (node (ref "Q2") (pin "3") (pinfunction "C_3") (pintype "passive"))
      (node (ref "R24") (pin "2") (pinfunction "2_2") (pintype "passive"))
    )
    (net (code "116") (name "Net-(Q3-B)") (class "Default")
      (node (ref "Q3") (pin "1") (pinfunction "B_1") (pintype "passive"))
      (node (ref "R29") (pin "1") (pinfunction "1_1") (pintype "passive"))
      (node (ref "R34") (pin "1") (pinfunction "1_1") (pintype "passive"))
    )
    (net (code "117") (name "Net-(Q3-C)") (class "Default")
      (node (ref "Q3") (pin "3") (pinfunction "C_3") (pintype "passive"))
      (node (ref "R25") (pin "2") (pinfunction "2_2") (pintype "passive"))
    )
    (net (code "118") (name "Net-(Q4-B)") (class "Default")
      (node (ref "Q4") (pin "1") (pinfunction "B_1") (pintype "passive"))
      (node (ref "R51") (pin "2") (pinfunction "2_2") (pintype "passive"))
    )
    (net (code "119") (name "Net-(R12-Pad2)") (class "Default")
      (node (ref "R12") (pin "2") (pinfunction "2_2") (pintype "passive"))
      (node (ref "R13") (pin "1") (pinfunction "1_1") (pintype "passive"))
    )
    (net (code "120") (name "Net-(R17-Pad2)") (class "Default")
      (node (ref "R17") (pin "2") (pinfunction "2_2") (pintype "passive"))
      (node (ref "R18") (pin "1") (pinfunction "1_1") (pintype "passive"))
    )
    (net (code "121") (name "Net-(Z2-K)") (class "Default")
      (node (ref "R4") (pin "1") (pinfunction "1_1") (pintype "passive"))
      (node (ref "R7") (pin "1") (pinfunction "1_1") (pintype "passive"))
      (node (ref "Z2") (pin "1") (pinfunction "K_1") (pintype "passive"))
    )
    (net (code "122") (name "OUT1") (class "Default")
      (node (ref "J2") (pin "1") (pinfunction "+_1") (pintype "passive"))
      (node (ref "J4") (pin "1") (pinfunction "+_1") (pintype "passive"))
      (node (ref "MOS3") (pin "10") (pinfunction "D_10") (pintype "passive"))
      (node (ref "MOS3") (pin "11") (pinfunction "D_11") (pintype "passive"))
      (node (ref "MOS3") (pin "5") (pinfunction "D_5") (pintype "passive"))
      (node (ref "MOS3") (pin "6") (pinfunction "D_6") (pintype "passive"))
      (node (ref "MOS3") (pin "7") (pinfunction "D_7") (pintype "passive"))
      (node (ref "MOS3") (pin "8") (pinfunction "D_8") (pintype "passive"))
      (node (ref "MOS3") (pin "9") (pinfunction "D_9") (pintype "passive"))
      (node (ref "R20") (pin "1") (pinfunction "1_1") (pintype "passive"))
    )
    (net (code "123") (name "OUT2") (class "Default")
      (node (ref "J3") (pin "1") (pinfunction "+_1") (pintype "passive"))
      (node (ref "J5") (pin "1") (pinfunction "+_1") (pintype "passive"))
      (node (ref "MOS4") (pin "10") (pinfunction "D_10") (pintype "passive"))
      (node (ref "MOS4") (pin "11") (pinfunction "D_11") (pintype "passive"))
      (node (ref "MOS4") (pin "5") (pinfunction "D_5") (pintype "passive"))
      (node (ref "MOS4") (pin "6") (pinfunction "D_6") (pintype "passive"))
      (node (ref "MOS4") (pin "7") (pinfunction "D_7") (pintype "passive"))
      (node (ref "MOS4") (pin "8") (pinfunction "D_8") (pintype "passive"))
      (node (ref "MOS4") (pin "9") (pinfunction "D_9") (pintype "passive"))
      (node (ref "R22") (pin "1") (pinfunction "1_1") (pintype "passive"))
    )
    (net (code "124") (name "PGND") (class "Default")
      (node (ref "BUZ1") (pin "2") (pinfunction "2_2") (pintype "passive"))
      (node (ref "C1") (pin "1") (pinfunction "1_1") (pintype "passive"))
      (node (ref "C10") (pin "1") (pinfunction "1_1") (pintype "passive"))
      (node (ref "C11") (pin "2") (pinfunction "2_2") (pintype "passive"))
      (node (ref "C13") (pin "1") (pinfunction "1_1") (pintype "passive"))
      (node (ref "C14") (pin "1") (pinfunction "1_1") (pintype "passive"))
      (node (ref "C15") (pin "1") (pinfunction "1_1") (pintype "passive"))
      (node (ref "C16") (pin "1") (pinfunction "1_1") (pintype "passive"))
      (node (ref "C17") (pin "1") (pinfunction "1_1") (pintype "passive"))
      (node (ref "C18") (pin "1") (pinfunction "1_1") (pintype "passive"))
      (node (ref "C19") (pin "1") (pinfunction "1_1") (pintype "passive"))
      (node (ref "C2") (pin "1") (pinfunction "1_1") (pintype "passive"))
      (node (ref "C20") (pin "1") (pinfunction "1_1") (pintype "passive"))
      (node (ref "C21") (pin "1") (pinfunction "1_1") (pintype "passive"))
      (node (ref "C23") (pin "2") (pinfunction "2_2") (pintype "passive"))
      (node (ref "C24") (pin "1") (pinfunction "1_1") (pintype "passive"))
      (node (ref "C25") (pin "1") (pinfunction "1_1") (pintype "passive"))
      (node (ref "C3") (pin "1") (pinfunction "1_1") (pintype "passive"))
      (node (ref "C4") (pin "1") (pinfunction "1_1") (pintype "passive"))
      (node (ref "C5") (pin "1") (pinfunction "1_1") (pintype "passive"))
      (node (ref "C7") (pin "1") (pinfunction "1_1") (pintype "passive"))
      (node (ref "D2") (pin "2") (pinfunction "A_2") (pintype "passive"))
      (node (ref "IC1") (pin "10") (pinfunction "GND_2_10") (pintype "passive"))
      (node (ref "IC1") (pin "13") (pinfunction "TEMP_13") (pintype "passive"))
      (node (ref "IC1") (pin "16") (pinfunction "SYNC_16") (pintype "passive"))
      (node (ref "IC1") (pin "17") (pinfunction "CLKOUT_17") (pintype "passive"))
      (node (ref "IC1") (pin "2") (pinfunction "GND_1_2") (pintype "passive"))
      (node (ref "IC1") (pin "33") (pinfunction "GND_3_33") (pintype "passive"))
      (node (ref "IC1") (pin "34") (pinfunction "GND_4_34") (pintype "passive"))
      (node (ref "IC1") (pin "35") (pinfunction "GND_5_35") (pintype "passive"))
      (node (ref "IC1") (pin "36") (pinfunction "GND_6_36") (pintype "passive"))
      (node (ref "IC1") (pin "37") (pinfunction "GND_7_37") (pintype "passive"))
      (node (ref "IC1") (pin "38") (pinfunction "GND_8_38") (pintype "passive"))
      (node (ref "IC1") (pin "MP1") (pinfunction "MP1_MP1") (pintype "passive"))
      (node (ref "IC1") (pin "MP2") (pinfunction "MP2_MP2") (pintype "passive"))
      (node (ref "IC1") (pin "MP3") (pinfunction "MP3_MP3") (pintype "passive"))
      (node (ref "IC1") (pin "MP4") (pinfunction "MP4_MP4") (pintype "passive"))
      (node (ref "IC3") (pin "1") (pinfunction "ADJ/GND_1") (pintype "power_in"))
      (node (ref "IC4") (pin "7") (pinfunction "GND_7") (pintype "passive"))
      (node (ref "J1") (pin "3") (pinfunction "SET_3") (pintype "passive"))
      (node (ref "J1") (pin "4") (pinfunction "SET_4") (pintype "passive"))
      (node (ref "J2") (pin "2") (pinfunction "-_2") (pintype "passive"))
      (node (ref "J3") (pin "2") (pinfunction "-_2") (pintype "passive"))
      (node (ref "J4") (pin "2") (pinfunction "-_2") (pintype "passive"))
      (node (ref "J5") (pin "2") (pinfunction "-_2") (pintype "passive"))
      (node (ref "J7") (pin "17") (pinfunction "17_17") (pintype "passive"))
      (node (ref "J7") (pin "18") (pinfunction "18_18") (pintype "passive"))
      (node (ref "J7") (pin "19") (pinfunction "19_19") (pintype "passive"))
      (node (ref "J7") (pin "20") (pinfunction "20_20") (pintype "passive"))
      (node (ref "J7") (pin "21") (pinfunction "21_21") (pintype "passive"))
      (node (ref "J7") (pin "22") (pinfunction "22_22") (pintype "passive"))
      (node (ref "J7") (pin "23") (pinfunction "23_23") (pintype "passive"))
      (node (ref "J7") (pin "24") (pinfunction "24_24") (pintype "passive"))
      (node (ref "LED1") (pin "2") (pinfunction "2_2") (pintype "passive"))
      (node (ref "LED2") (pin "2") (pinfunction "2_2") (pintype "passive"))
      (node (ref "LED3") (pin "2") (pinfunction "2_2") (pintype "passive"))
      (node (ref "MOS2") (pin "1") (pinfunction "S_1") (pintype "passive"))
      (node (ref "MOS2") (pin "2") (pinfunction "S_2") (pintype "passive"))
      (node (ref "MOS2") (pin "3") (pinfunction "S_3") (pintype "passive"))
      (node (ref "Q2") (pin "2") (pinfunction "E_2") (pintype "passive"))
      (node (ref "Q3") (pin "2") (pinfunction "E_2") (pintype "passive"))
      (node (ref "R10") (pin "2") (pinfunction "2_2") (pintype "passive"))
      (node (ref "R11") (pin "1") (pinfunction "1_1") (pintype "passive"))
      (node (ref "R13") (pin "2") (pinfunction "2_2") (pintype "passive"))
      (node (ref "R14") (pin "1") (pinfunction "1_1") (pintype "passive"))
      (node (ref "R15") (pin "2") (pinfunction "2_2") (pintype "passive"))
      (node (ref "R18") (pin "2") (pinfunction "2_2") (pintype "passive"))
      (node (ref "R30") (pin "1") (pinfunction "1_1") (pintype "passive"))
      (node (ref "R31") (pin "1") (pinfunction "1_1") (pintype "passive"))
      (node (ref "R32") (pin "1") (pinfunction "1_1") (pintype "passive"))
      (node (ref "R33") (pin "2") (pinfunction "2_2") (pintype "passive"))
      (node (ref "R34") (pin "2") (pinfunction "2_2") (pintype "passive"))
      (node (ref "R35") (pin "1") (pinfunction "1_1") (pintype "passive"))
      (node (ref "R36") (pin "1") (pinfunction "1_1") (pintype "passive"))
      (node (ref "TP2") (pin "1") (pinfunction "1_1") (pintype "passive"))
      (node (ref "Z1") (pin "2") (pinfunction "2_2") (pintype "passive"))
    )
    (net (code "125") (name "VCC_3V3_MCU") (class "Default")
      (node (ref "C35") (pin "2") (pinfunction "2_2") (pintype "passive"))
      (node (ref "C36") (pin "2") (pinfunction "2_2") (pintype "passive"))
      (node (ref "C37") (pin "2") (pinfunction "2_2") (pintype "passive"))
      (node (ref "C40") (pin "2") (pinfunction "2_2") (pintype "passive"))
      (node (ref "C41") (pin "2") (pinfunction "2_2") (pintype "passive"))
      (node (ref "IC5") (pin "5") (pinfunction "VIO_5") (pintype "passive"))
      (node (ref "IC6") (pin "5") (pinfunction "VIO_5") (pintype "passive"))
      (node (ref "IC7") (pin "B2") (pinfunction "VBAT_B2") (pintype "passive"))
      (node (ref "IC7") (pin "D2") (pinfunction "VDD_1_D2") (pintype "passive"))
      (node (ref "IC7") (pin "F4") (pinfunction "VDD_2_F4") (pintype "passive"))
      (node (ref "IC7") (pin "F5") (pinfunction "VDD_3_F5") (pintype "passive"))
      (node (ref "IC7") (pin "F6") (pinfunction "VDDUSB_F6") (pintype "passive"))
      (node (ref "IC7") (pin "F7") (pinfunction "PDR_ON_F7") (pintype "passive"))
      (node (ref "IC7") (pin "H1") (pinfunction "VDDA_H1") (pintype "passive"))
      (node (ref "IC7") (pin "K1") (pinfunction "VDD_4_K1") (pintype "passive"))
      (node (ref "IC8") (pin "5") (pinfunction "VIO_5") (pintype "passive"))
      (node (ref "IC9") (pin "5") (pinfunction "OUT_5") (pintype "passive"))
      (node (ref "J8") (pin "4") (pinfunction "VDD_4") (pintype "passive"))
      (node (ref "R37") (pin "2") (pinfunction "2_2") (pintype "passive"))
      (node (ref "R38") (pin "2") (pinfunction "2_2") (pintype "passive"))
      (node (ref "R39") (pin "2") (pinfunction "2_2") (pintype "passive"))
      (node (ref "R40") (pin "2") (pinfunction "2_2") (pintype "passive"))
      (node (ref "R41") (pin "2") (pinfunction "2_2") (pintype "passive"))
      (node (ref "R42") (pin "2") (pinfunction "2_2") (pintype "passive"))
      (node (ref "R44") (pin "2") (pinfunction "2_2") (pintype "passive"))
      (node (ref "R45") (pin "2") (pinfunction "2_2") (pintype "passive"))
      (node (ref "R46") (pin "2") (pinfunction "2_2") (pintype "passive"))
      (node (ref "R47") (pin "2") (pinfunction "2_2") (pintype "passive"))
      (node (ref "R48") (pin "2") (pinfunction "2_2") (pintype "passive"))
      (node (ref "R50") (pin "2") (pinfunction "2_2") (pintype "passive"))
      (node (ref "R53") (pin "2") (pinfunction "2_2") (pintype "passive"))
      (node (ref "R54") (pin "1") (pinfunction "1_1") (pintype "passive"))
      (node (ref "R55") (pin "1") (pinfunction "1_1") (pintype "passive"))
      (node (ref "R57") (pin "1") (pinfunction "1_1") (pintype "passive"))
      (node (ref "R58") (pin "1") (pinfunction "1_1") (pintype "passive"))
      (node (ref "S1") (pin "1") (pinfunction "1_1") (pintype "passive"))
    )
    (net (code "126") (name "VCC_3V3_OUT") (class "Default")
      (node (ref "BUZ1") (pin "1") (pinfunction "1_1") (pintype "passive"))
      (node (ref "C17") (pin "2") (pinfunction "2_2") (pintype "passive"))
      (node (ref "C18") (pin "2") (pinfunction "2_2") (pintype "passive"))
      (node (ref "IC3") (pin "6") (pinfunction "VOUT_1_6") (pintype "output"))
      (node (ref "IC3") (pin "7") (pinfunction "VOUT_2_7") (pintype "output"))
      (node (ref "IC3") (pin "8") (pinfunction "VOUT_3_8") (pintype "output"))
      (node (ref "IC3") (pin "9") (pinfunction "VOUT_4_9") (pintype "output"))
      (node (ref "TP1") (pin "1") (pinfunction "1_1") (pintype "passive"))
    )
    (net (code "127") (name "VCC_5V_IC") (class "Default")
      (node (ref "C13") (pin "2") (pinfunction "2_2") (pintype "passive"))
      (node (ref "C14") (pin "2") (pinfunction "2_2") (pintype "passive"))
      (node (ref "C26") (pin "2") (pinfunction "2_2") (pintype "passive"))
      (node (ref "C28") (pin "2") (pinfunction "2_2") (pintype "passive"))
      (node (ref "C29") (pin "2") (pinfunction "2_2") (pintype "passive"))
      (node (ref "C38") (pin "2") (pinfunction "2_2") (pintype "passive"))
      (node (ref "C39") (pin "2") (pinfunction "2_2") (pintype "passive"))
      (node (ref "IC5") (pin "3") (pinfunction "VCC_3") (pintype "passive"))
      (node (ref "IC6") (pin "3") (pinfunction "VCC_3") (pintype "passive"))
      (node (ref "IC8") (pin "3") (pinfunction "VCC_3") (pintype "passive"))
      (node (ref "IC9") (pin "1") (pinfunction "IN_1") (pintype "passive"))
      (node (ref "IC9") (pin "3") (pinfunction "EN_3") (pintype "passive"))
      (node (ref "J12") (pin "4") (pinfunction "4_4") (pintype "passive"))
      (node (ref "J13") (pin "4") (pinfunction "4_4") (pintype "passive"))
      (node (ref "J14") (pin "4") (pinfunction "4_4") (pintype "passive"))
      (node (ref "J19") (pin "4") (pinfunction "4_4") (pintype "passive"))
      (node (ref "J20") (pin "4") (pinfunction "4_4") (pintype "passive"))
      (node (ref "J21") (pin "4") (pinfunction "4_4") (pintype "passive"))
      (node (ref "J25") (pin "4") (pinfunction "4_4") (pintype "passive"))
      (node (ref "J26") (pin "4") (pinfunction "4_4") (pintype "passive"))
      (node (ref "J6") (pin "A4") (pinfunction "VBUS_1_A4") (pintype "passive"))
      (node (ref "J6") (pin "A9") (pinfunction "VBUS_2_A9") (pintype "passive"))
      (node (ref "J6") (pin "B4") (pinfunction "VBUS_3_B4") (pintype "passive"))
      (node (ref "J6") (pin "B9") (pinfunction "VBUS_4_B9") (pintype "passive"))
      (node (ref "J9") (pin "2") (pinfunction "2_2") (pintype "passive"))
      (node (ref "L3") (pin "2") (pinfunction "2_2") (pintype "passive"))
      (node (ref "R23") (pin "1") (pinfunction "1_1") (pintype "passive"))
      (node (ref "R26") (pin "2") (pinfunction "2_2") (pintype "passive"))
    )
    (net (code "128") (name "VCC_ADJ_MOTOR") (class "Default")
      (node (ref "C1") (pin "2") (pinfunction "2_2") (pintype "passive"))
      (node (ref "C2") (pin "2") (pinfunction "2_2") (pintype "passive"))
      (node (ref "IC1") (pin "26") (pinfunction "BIAS_26") (pintype "passive"))
      (node (ref "J7") (pin "10") (pinfunction "10_10") (pintype "passive"))
      (node (ref "J7") (pin "11") (pinfunction "11_11") (pintype "passive"))
      (node (ref "J7") (pin "12") (pinfunction "12_12") (pintype "passive"))
      (node (ref "J7") (pin "13") (pinfunction "13_13") (pintype "passive"))
      (node (ref "J7") (pin "14") (pinfunction "14_14") (pintype "passive"))
      (node (ref "J7") (pin "15") (pinfunction "15_15") (pintype "passive"))
      (node (ref "J7") (pin "16") (pinfunction "16_16") (pintype "passive"))
      (node (ref "J7") (pin "9") (pinfunction "9_9") (pintype "passive"))
      (node (ref "L1") (pin "2") (pinfunction "2_2") (pintype "passive"))
      (node (ref "L2") (pin "2") (pinfunction "2_2") (pintype "passive"))
      (node (ref "R16") (pin "2") (pinfunction "2_2") (pintype "passive"))
      (node (ref "R6") (pin "1") (pinfunction "1_1") (pintype "passive"))
    )
    (net (code "129") (name "VCC_INPUT") (class "Default")
      (node (ref "C15") (pin "2") (pinfunction "2_2") (pintype "passive"))
      (node (ref "C16") (pin "2") (pinfunction "2_2") (pintype "passive"))
      (node (ref "C19") (pin "2") (pinfunction "2_2") (pintype "passive"))
      (node (ref "C20") (pin "2") (pinfunction "2_2") (pintype "passive"))
      (node (ref "C3") (pin "2") (pinfunction "2_2") (pintype "passive"))
      (node (ref "C4") (pin "2") (pinfunction "2_2") (pintype "passive"))
      (node (ref "IC1") (pin "11") (pinfunction "EN1_11") (pintype "passive"))
      (node (ref "IC1") (pin "12") (pinfunction "EN2_12") (pintype "passive"))
      (node (ref "IC1") (pin "4") (pinfunction "VIN1_1_4") (pintype "passive"))
      (node (ref "IC1") (pin "5") (pinfunction "VIN1_2_5") (pintype "passive"))
      (node (ref "IC1") (pin "7") (pinfunction "VIN2_1_7") (pintype "passive"))
      (node (ref "IC1") (pin "8") (pinfunction "VIN2_2_8") (pintype "passive"))
      (node (ref "IC3") (pin "2") (pinfunction "VIN_2") (pintype "input"))
      (node (ref "IC4") (pin "2") (pinfunction "VIN_2") (pintype "passive"))
      (node (ref "MOS1") (pin "10") (pinfunction "D_10") (pintype "passive"))
      (node (ref "MOS1") (pin "11") (pinfunction "D_11") (pintype "passive"))
      (node (ref "MOS1") (pin "5") (pinfunction "D_5") (pintype "passive"))
      (node (ref "MOS1") (pin "6") (pinfunction "D_6") (pintype "passive"))
      (node (ref "MOS1") (pin "7") (pinfunction "D_7") (pintype "passive"))
      (node (ref "MOS1") (pin "8") (pinfunction "D_8") (pintype "passive"))
      (node (ref "MOS1") (pin "9") (pinfunction "D_9") (pintype "passive"))
      (node (ref "MOS3") (pin "1") (pinfunction "1_1") (pintype "passive"))
      (node (ref "MOS3") (pin "2") (pinfunction "2_2") (pintype "passive"))
      (node (ref "MOS3") (pin "3") (pinfunction "3_3") (pintype "passive"))
      (node (ref "MOS4") (pin "1") (pinfunction "1_1") (pintype "passive"))
      (node (ref "MOS4") (pin "2") (pinfunction "2_2") (pintype "passive"))
      (node (ref "MOS4") (pin "3") (pinfunction "3_3") (pintype "passive"))
      (node (ref "R19") (pin "1") (pinfunction "1_1") (pintype "passive"))
      (node (ref "R21") (pin "1") (pinfunction "1_1") (pintype "passive"))
      (node (ref "R27") (pin "2") (pinfunction "2_2") (pintype "passive"))
      (node (ref "R5") (pin "2") (pinfunction "2_2") (pintype "passive"))
      (node (ref "Z3") (pin "1") (pinfunction "1_1") (pintype "passive"))
      (node (ref "Z4") (pin "1") (pinfunction "1_1") (pintype "passive"))
    )
    (net (code "130") (name "unconnected-(IC1-BST1-Pad24)") (class "Default")
      (node (ref "IC1") (pin "24") (pinfunction "BST1_24") (pintype "passive+no_connect"))
    )
    (net (code "131") (name "unconnected-(IC1-BST2-Pad18)") (class "Default")
      (node (ref "IC1") (pin "18") (pinfunction "BST2_18") (pintype "passive+no_connect"))
    )
    (net (code "132") (name "unconnected-(IC3-N{slash}C_1-Pad3)") (class "Default")
      (node (ref "IC3") (pin "3") (pinfunction "N/C_1_3") (pintype "passive+no_connect"))
    )
    (net (code "133") (name "unconnected-(IC3-N{slash}C_2-Pad4)") (class "Default")
      (node (ref "IC3") (pin "4") (pinfunction "N/C_2_4") (pintype "passive+no_connect"))
    )
    (net (code "134") (name "unconnected-(IC3-N{slash}C_3-Pad5)") (class "Default")
      (node (ref "IC3") (pin "5") (pinfunction "N/C_3_5") (pintype "passive+no_connect"))
    )
    (net (code "135") (name "unconnected-(IC7A-PC14_OSC32_IN-PadA1)") (class "Default")
      (node (ref "IC7") (pin "A1") (pinfunction "PC14_OSC32_IN_A1") (pintype "passive+no_connect"))
    )
    (net (code "136") (name "unconnected-(IC7A-PC15_OSC32_OUT-PadB1)") (class "Default")
      (node (ref "IC7") (pin "B1") (pinfunction "PC15_OSC32_OUT_B1") (pintype "passive+no_connect"))
    )
    (net (code "137") (name "unconnected-(IC7B-PA4-PadG3)") (class "Default")
      (node (ref "IC7") (pin "G3") (pinfunction "PA4_G3") (pintype "passive"))
    )
    (net (code "138") (name "unconnected-(IC7B-PA5-PadH3)") (class "Default")
      (node (ref "IC7") (pin "H3") (pinfunction "PA5_H3") (pintype "passive"))
    )
    (net (code "139") (name "unconnected-(IC7B-PA6-PadJ3)") (class "Default")
      (node (ref "IC7") (pin "J3") (pinfunction "PA6_J3") (pintype "passive"))
    )
    (net (code "140") (name "unconnected-(IC7B-PB2-PadG5)") (class "Default")
      (node (ref "IC7") (pin "G5") (pinfunction "PB2_G5") (pintype "passive"))
    )
    (net (code "141") (name "unconnected-(IC7B-PB5-PadC5)") (class "Default")
      (node (ref "IC7") (pin "C5") (pinfunction "PB5_C5") (pintype "passive"))
    )
    (net (code "142") (name "unconnected-(IC7B-PC1-PadF2)") (class "Default")
      (node (ref "IC7") (pin "F2") (pinfunction "PC1_F2") (pintype "passive"))
    )
    (net (code "143") (name "unconnected-(IC7B-PC2-PadE2)") (class "Default")
      (node (ref "IC7") (pin "E2") (pinfunction "PC2_E2") (pintype "passive"))
    )
    (net (code "144") (name "unconnected-(IC7B-PC3-PadF3)") (class "Default")
      (node (ref "IC7") (pin "F3") (pinfunction "PC3_F3") (pintype "passive"))
    )
    (net (code "145") (name "unconnected-(IC7B-PC4-PadG4)") (class "Default")
      (node (ref "IC7") (pin "G4") (pinfunction "PC4_G4") (pintype "passive"))
    )
    (net (code "146") (name "unconnected-(IC7B-PC5-PadH4)") (class "Default")
      (node (ref "IC7") (pin "H4") (pinfunction "PC5_H4") (pintype "passive"))
    )
    (net (code "147") (name "unconnected-(IC7B-PD1-PadE8)") (class "Default")
      (node (ref "IC7") (pin "E8") (pinfunction "PD1_E8") (pintype "passive"))
    )
    (net (code "148") (name "unconnected-(IC7B-PD3-PadC7)") (class "Default")
      (node (ref "IC7") (pin "C7") (pinfunction "PD3_C7") (pintype "passive"))
    )
    (net (code "149") (name "unconnected-(IC7B-PD5-PadB6)") (class "Default")
      (node (ref "IC7") (pin "B6") (pinfunction "PD5_B6") (pintype "passive"))
    )
    (net (code "150") (name "unconnected-(IC7B-PD6-PadC6)") (class "Default")
      (node (ref "IC7") (pin "C6") (pinfunction "PD6_C6") (pintype "passive"))
    )
    (net (code "151") (name "unconnected-(IC7B-PD7-PadD6)") (class "Default")
      (node (ref "IC7") (pin "D6") (pinfunction "PD7_D6") (pintype "passive"))
    )
    (net (code "152") (name "unconnected-(IC7B-PD11-PadG9)") (class "Default")
      (node (ref "IC7") (pin "G9") (pinfunction "PD11_G9") (pintype "passive"))
    )
    (net (code "153") (name "unconnected-(IC7B-PD14-PadH8)") (class "Default")
      (node (ref "IC7") (pin "H8") (pinfunction "PD14_H8") (pintype "passive"))
    )
    (net (code "154") (name "unconnected-(IC7B-PD15-PadG8)") (class "Default")
      (node (ref "IC7") (pin "G8") (pinfunction "PD15_G8") (pintype "passive"))
    )
    (net (code "155") (name "unconnected-(IC7B-PE4-PadC3)") (class "Default")
      (node (ref "IC7") (pin "C3") (pinfunction "PE4_C3") (pintype "passive"))
    )
    (net (code "156") (name "unconnected-(IC7B-PE5-PadD3)") (class "Default")
      (node (ref "IC7") (pin "D3") (pinfunction "PE5_D3") (pintype "passive"))
    )
    (net (code "157") (name "unconnected-(IC7B-PE7-PadH5)") (class "Default")
      (node (ref "IC7") (pin "H5") (pinfunction "PE7_H5") (pintype "passive"))
    )
    (net (code "158") (name "unconnected-(IC7B-PE10-PadG6)") (class "Default")
      (node (ref "IC7") (pin "G6") (pinfunction "PE10_G6") (pintype "passive"))
    )
    (net (code "159") (name "unconnected-(IC7B-PE11-PadH6)") (class "Default")
      (node (ref "IC7") (pin "H6") (pinfunction "PE11_H6") (pintype "passive"))
    )
    (net (code "160") (name "unconnected-(IC7B-PE14-PadG7)") (class "Default")
      (node (ref "IC7") (pin "G7") (pinfunction "PE14_G7") (pintype "passive"))
    )
    (net (code "161") (name "unconnected-(IC7B-PE15-PadH7)") (class "Default")
      (node (ref "IC7") (pin "H7") (pinfunction "PE15_H7") (pintype "passive"))
    )
    (net (code "162") (name "unconnected-(IC9-N{slash}C-Pad4)") (class "Default")
      (node (ref "IC9") (pin "4") (pinfunction "N/C_4") (pintype "passive+no_connect"))
    )
    (net (code "163") (name "unconnected-(J10-PadMP1)") (class "Default")
      (node (ref "J10") (pin "MP1") (pinfunction "MP1_MP1") (pintype "passive+no_connect"))
    )
    (net (code "164") (name "unconnected-(J10-PadMP2)") (class "Default")
      (node (ref "J10") (pin "MP2") (pinfunction "MP2_MP2") (pintype "passive+no_connect"))
    )
    (net (code "165") (name "unconnected-(J11-PadMP1)") (class "Default")
      (node (ref "J11") (pin "MP1") (pinfunction "MP1_MP1") (pintype "passive+no_connect"))
    )
    (net (code "166") (name "unconnected-(J11-PadMP2)") (class "Default")
      (node (ref "J11") (pin "MP2") (pinfunction "MP2_MP2") (pintype "passive+no_connect"))
    )
    (net (code "167") (name "unconnected-(J12-PadMP1)") (class "Default")
      (node (ref "J12") (pin "MP1") (pinfunction "MP1_MP1") (pintype "passive+no_connect"))
    )
    (net (code "168") (name "unconnected-(J12-PadMP2)") (class "Default")
      (node (ref "J12") (pin "MP2") (pinfunction "MP2_MP2") (pintype "passive+no_connect"))
    )
    (net (code "169") (name "unconnected-(J13-PadMP1)") (class "Default")
      (node (ref "J13") (pin "MP1") (pinfunction "MP1_MP1") (pintype "passive+no_connect"))
    )
    (net (code "170") (name "unconnected-(J13-PadMP2)") (class "Default")
      (node (ref "J13") (pin "MP2") (pinfunction "MP2_MP2") (pintype "passive+no_connect"))
    )
    (net (code "171") (name "unconnected-(J14-PadMP1)") (class "Default")
      (node (ref "J14") (pin "MP1") (pinfunction "MP1_MP1") (pintype "passive+no_connect"))
    )
    (net (code "172") (name "unconnected-(J14-PadMP2)") (class "Default")
      (node (ref "J14") (pin "MP2") (pinfunction "MP2_MP2") (pintype "passive+no_connect"))
    )
    (net (code "173") (name "unconnected-(J15-PadMP1)") (class "Default")
      (node (ref "J15") (pin "MP1") (pinfunction "MP1_MP1") (pintype "passive+no_connect"))
    )
    (net (code "174") (name "unconnected-(J15-PadMP2)") (class "Default")
      (node (ref "J15") (pin "MP2") (pinfunction "MP2_MP2") (pintype "passive+no_connect"))
    )
    (net (code "175") (name "unconnected-(J16-PadMP1)") (class "Default")
      (node (ref "J16") (pin "MP1") (pinfunction "MP1_MP1") (pintype "passive+no_connect"))
    )
    (net (code "176") (name "unconnected-(J16-PadMP2)") (class "Default")
      (node (ref "J16") (pin "MP2") (pinfunction "MP2_MP2") (pintype "passive+no_connect"))
    )
    (net (code "177") (name "unconnected-(J17-PadMP1)") (class "Default")
      (node (ref "J17") (pin "MP1") (pinfunction "MP1_MP1") (pintype "passive+no_connect"))
    )
    (net (code "178") (name "unconnected-(J17-PadMP2)") (class "Default")
      (node (ref "J17") (pin "MP2") (pinfunction "MP2_MP2") (pintype "passive+no_connect"))
    )
    (net (code "179") (name "unconnected-(J18-PadMP1)") (class "Default")
      (node (ref "J18") (pin "MP1") (pinfunction "MP1_MP1") (pintype "passive+no_connect"))
    )
    (net (code "180") (name "unconnected-(J18-PadMP2)") (class "Default")
      (node (ref "J18") (pin "MP2") (pinfunction "MP2_MP2") (pintype "passive+no_connect"))
    )
    (net (code "181") (name "unconnected-(J19-PadMP1)") (class "Default")
      (node (ref "J19") (pin "MP1") (pinfunction "MP1_MP1") (pintype "passive+no_connect"))
    )
    (net (code "182") (name "unconnected-(J19-PadMP2)") (class "Default")
      (node (ref "J19") (pin "MP2") (pinfunction "MP2_MP2") (pintype "passive+no_connect"))
    )
    (net (code "183") (name "unconnected-(J20-PadMP1)") (class "Default")
      (node (ref "J20") (pin "MP1") (pinfunction "MP1_MP1") (pintype "passive+no_connect"))
    )
    (net (code "184") (name "unconnected-(J20-PadMP2)") (class "Default")
      (node (ref "J20") (pin "MP2") (pinfunction "MP2_MP2") (pintype "passive+no_connect"))
    )
    (net (code "185") (name "unconnected-(J21-PadMP1)") (class "Default")
      (node (ref "J21") (pin "MP1") (pinfunction "MP1_MP1") (pintype "passive+no_connect"))
    )
    (net (code "186") (name "unconnected-(J21-PadMP2)") (class "Default")
      (node (ref "J21") (pin "MP2") (pinfunction "MP2_MP2") (pintype "passive+no_connect"))
    )
    (net (code "187") (name "unconnected-(J22-PadMP1)") (class "Default")
      (node (ref "J22") (pin "MP1") (pinfunction "MP1_MP1") (pintype "passive+no_connect"))
    )
    (net (code "188") (name "unconnected-(J22-PadMP2)") (class "Default")
      (node (ref "J22") (pin "MP2") (pinfunction "MP2_MP2") (pintype "passive+no_connect"))
    )
    (net (code "189") (name "unconnected-(J23-PadMP1)") (class "Default")
      (node (ref "J23") (pin "MP1") (pinfunction "MP1_MP1") (pintype "passive+no_connect"))
    )
    (net (code "190") (name "unconnected-(J23-PadMP2)") (class "Default")
      (node (ref "J23") (pin "MP2") (pinfunction "MP2_MP2") (pintype "passive+no_connect"))
    )
    (net (code "191") (name "unconnected-(J24-PadMP1)") (class "Default")
      (node (ref "J24") (pin "MP1") (pinfunction "MP1_MP1") (pintype "passive+no_connect"))
    )
    (net (code "192") (name "unconnected-(J24-PadMP2)") (class "Default")
      (node (ref "J24") (pin "MP2") (pinfunction "MP2_MP2") (pintype "passive+no_connect"))
    )
    (net (code "193") (name "unconnected-(J25-PadMP1)") (class "Default")
      (node (ref "J25") (pin "MP1") (pinfunction "MP1_MP1") (pintype "passive+no_connect"))
    )
    (net (code "194") (name "unconnected-(J25-PadMP2)") (class "Default")
      (node (ref "J25") (pin "MP2") (pinfunction "MP2_MP2") (pintype "passive+no_connect"))
    )
    (net (code "195") (name "unconnected-(J26-PadMP1)") (class "Default")
      (node (ref "J26") (pin "MP1") (pinfunction "MP1_MP1") (pintype "passive+no_connect"))
    )
    (net (code "196") (name "unconnected-(J26-PadMP2)") (class "Default")
      (node (ref "J26") (pin "MP2") (pinfunction "MP2_MP2") (pintype "passive+no_connect"))
    )
    (net (code "197") (name "unconnected-(J27-PadMP1)") (class "Default")
      (node (ref "J27") (pin "MP1") (pinfunction "MP1_MP1") (pintype "passive+no_connect"))
    )
    (net (code "198") (name "unconnected-(J27-PadMP2)") (class "Default")
      (node (ref "J27") (pin "MP2") (pinfunction "MP2_MP2") (pintype "passive+no_connect"))
    )
    (net (code "199") (name "unconnected-(J28-PadMP1)") (class "Default")
      (node (ref "J28") (pin "MP1") (pinfunction "MP1_MP1") (pintype "passive+no_connect"))
    )
    (net (code "200") (name "unconnected-(J28-PadMP2)") (class "Default")
      (node (ref "J28") (pin "MP2") (pinfunction "MP2_MP2") (pintype "passive+no_connect"))
    )
  )
)
